# Trace_4__2_8TFT__AT32F435RGT7.net
KiCad netlist of a schematic drawn in EasyEDA Pro
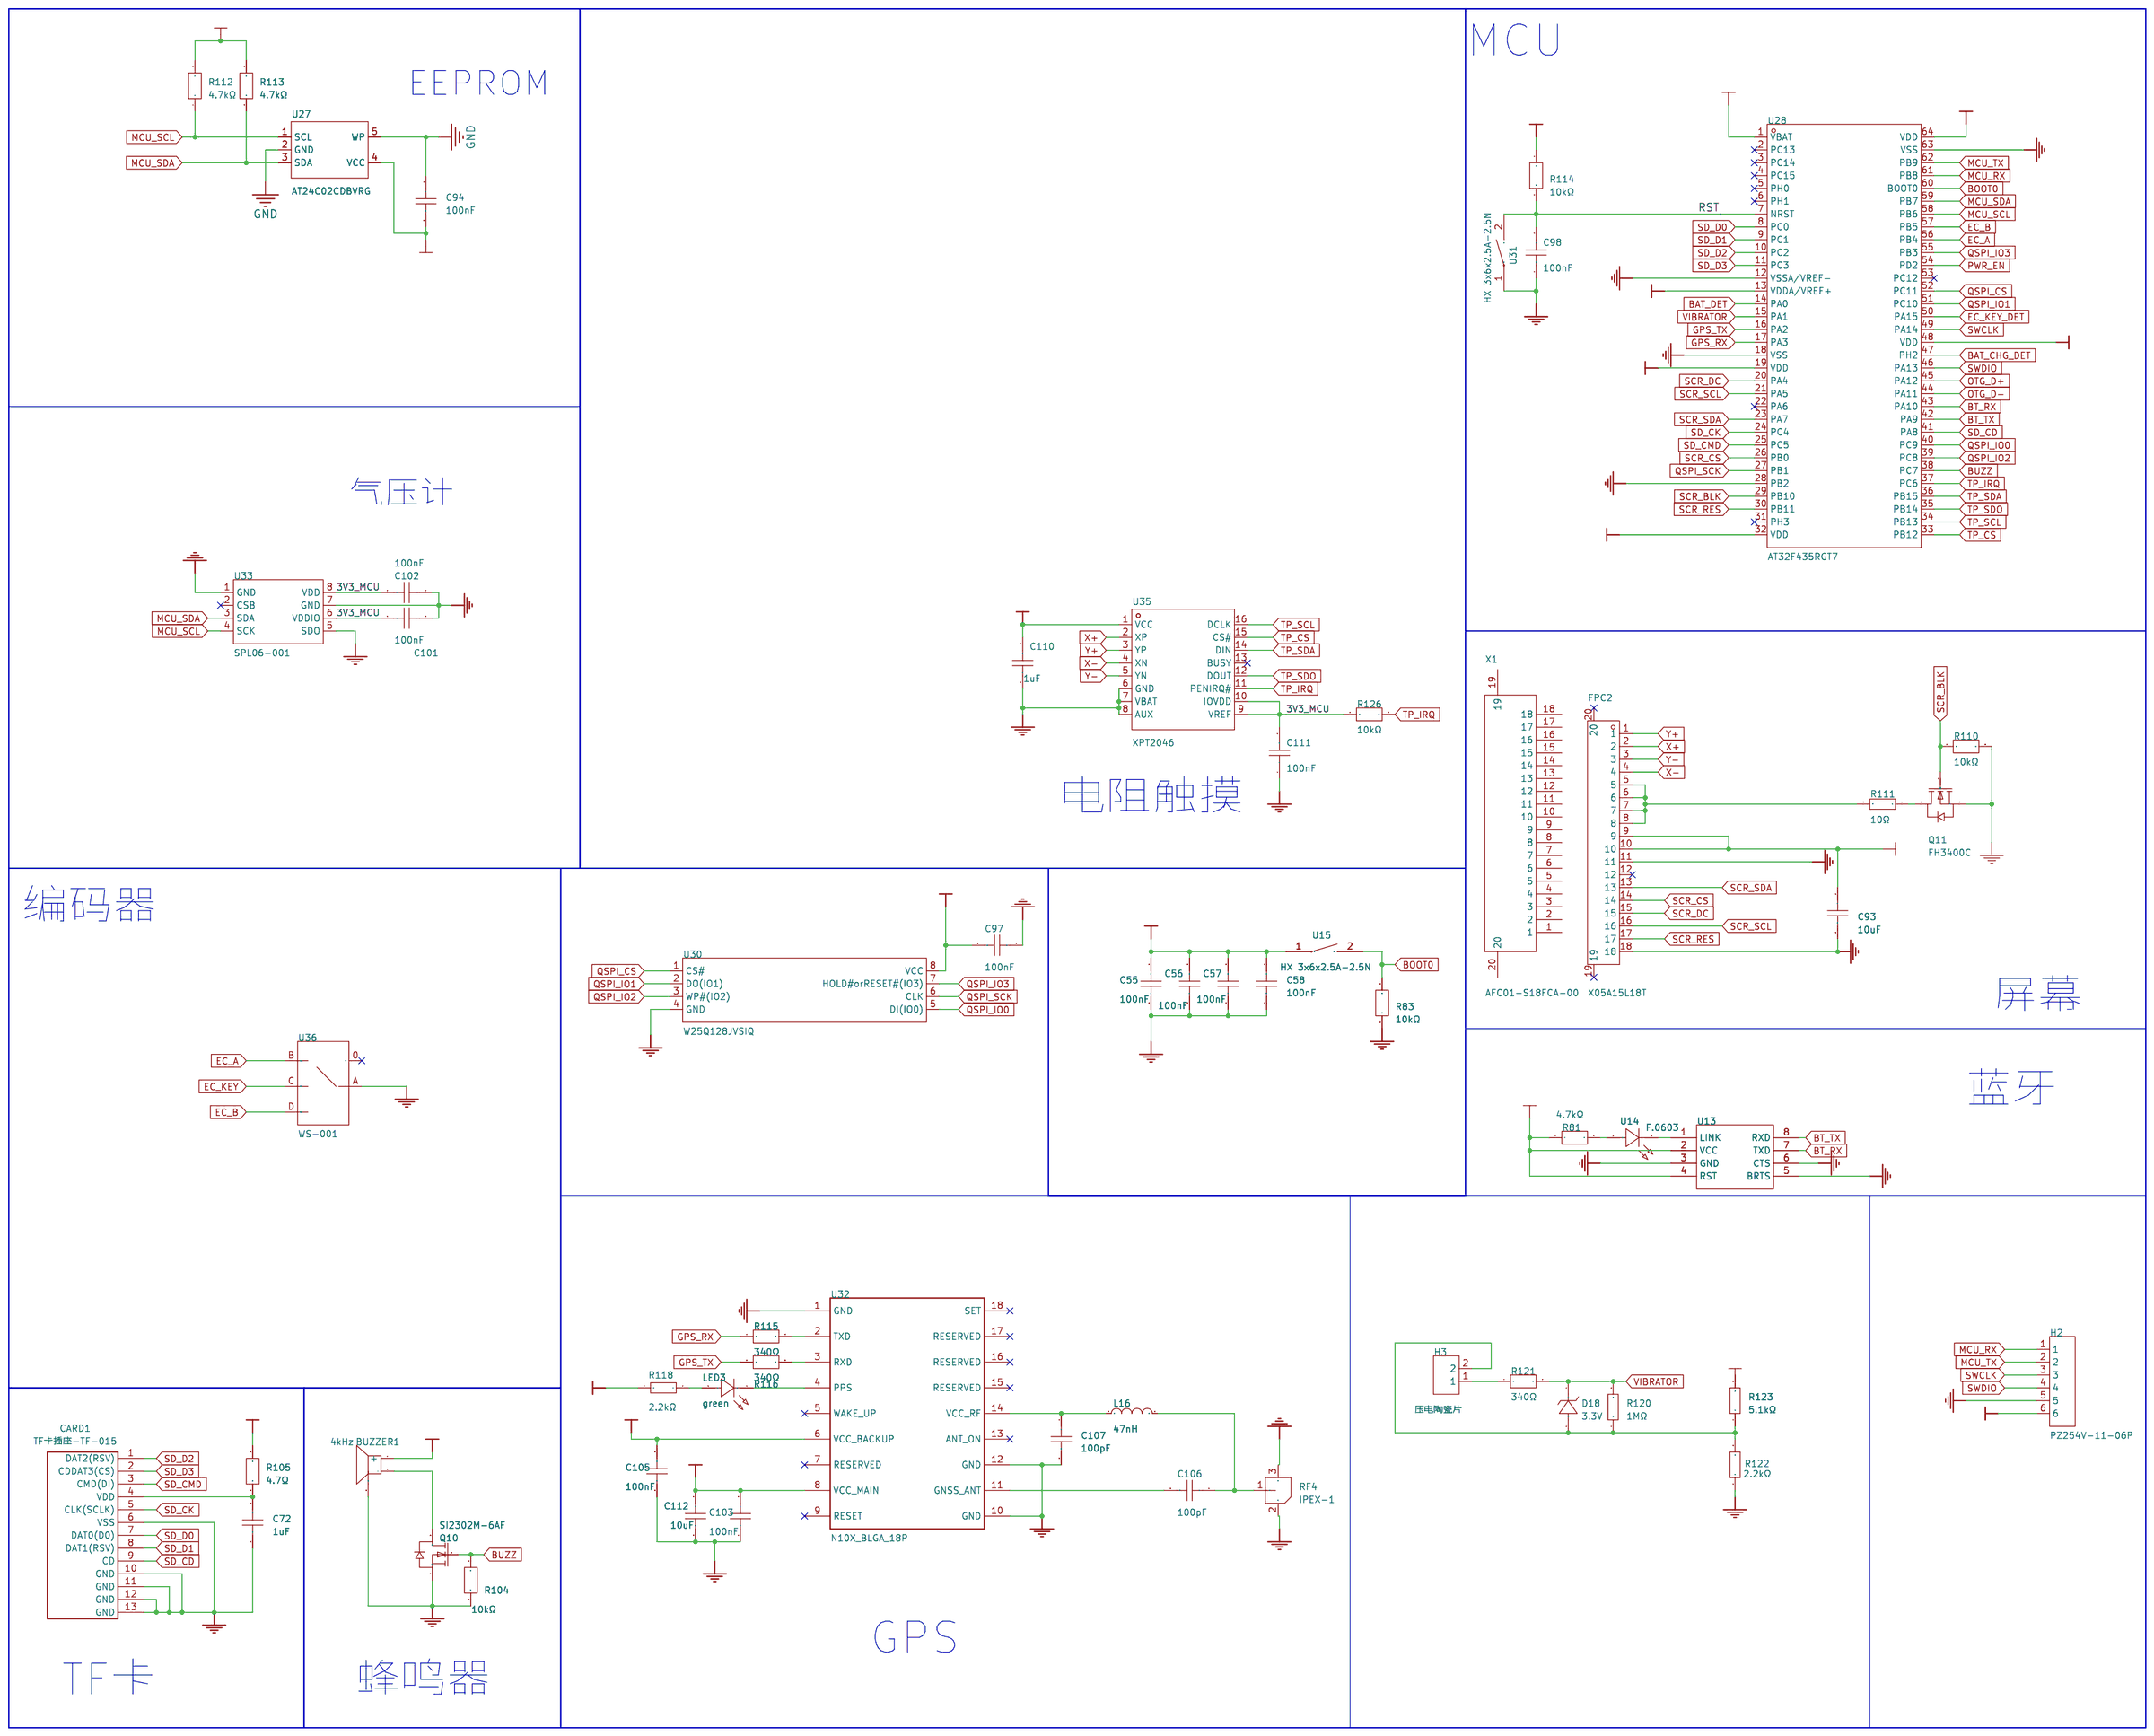
[diagram p0: Sheet_1 copy]
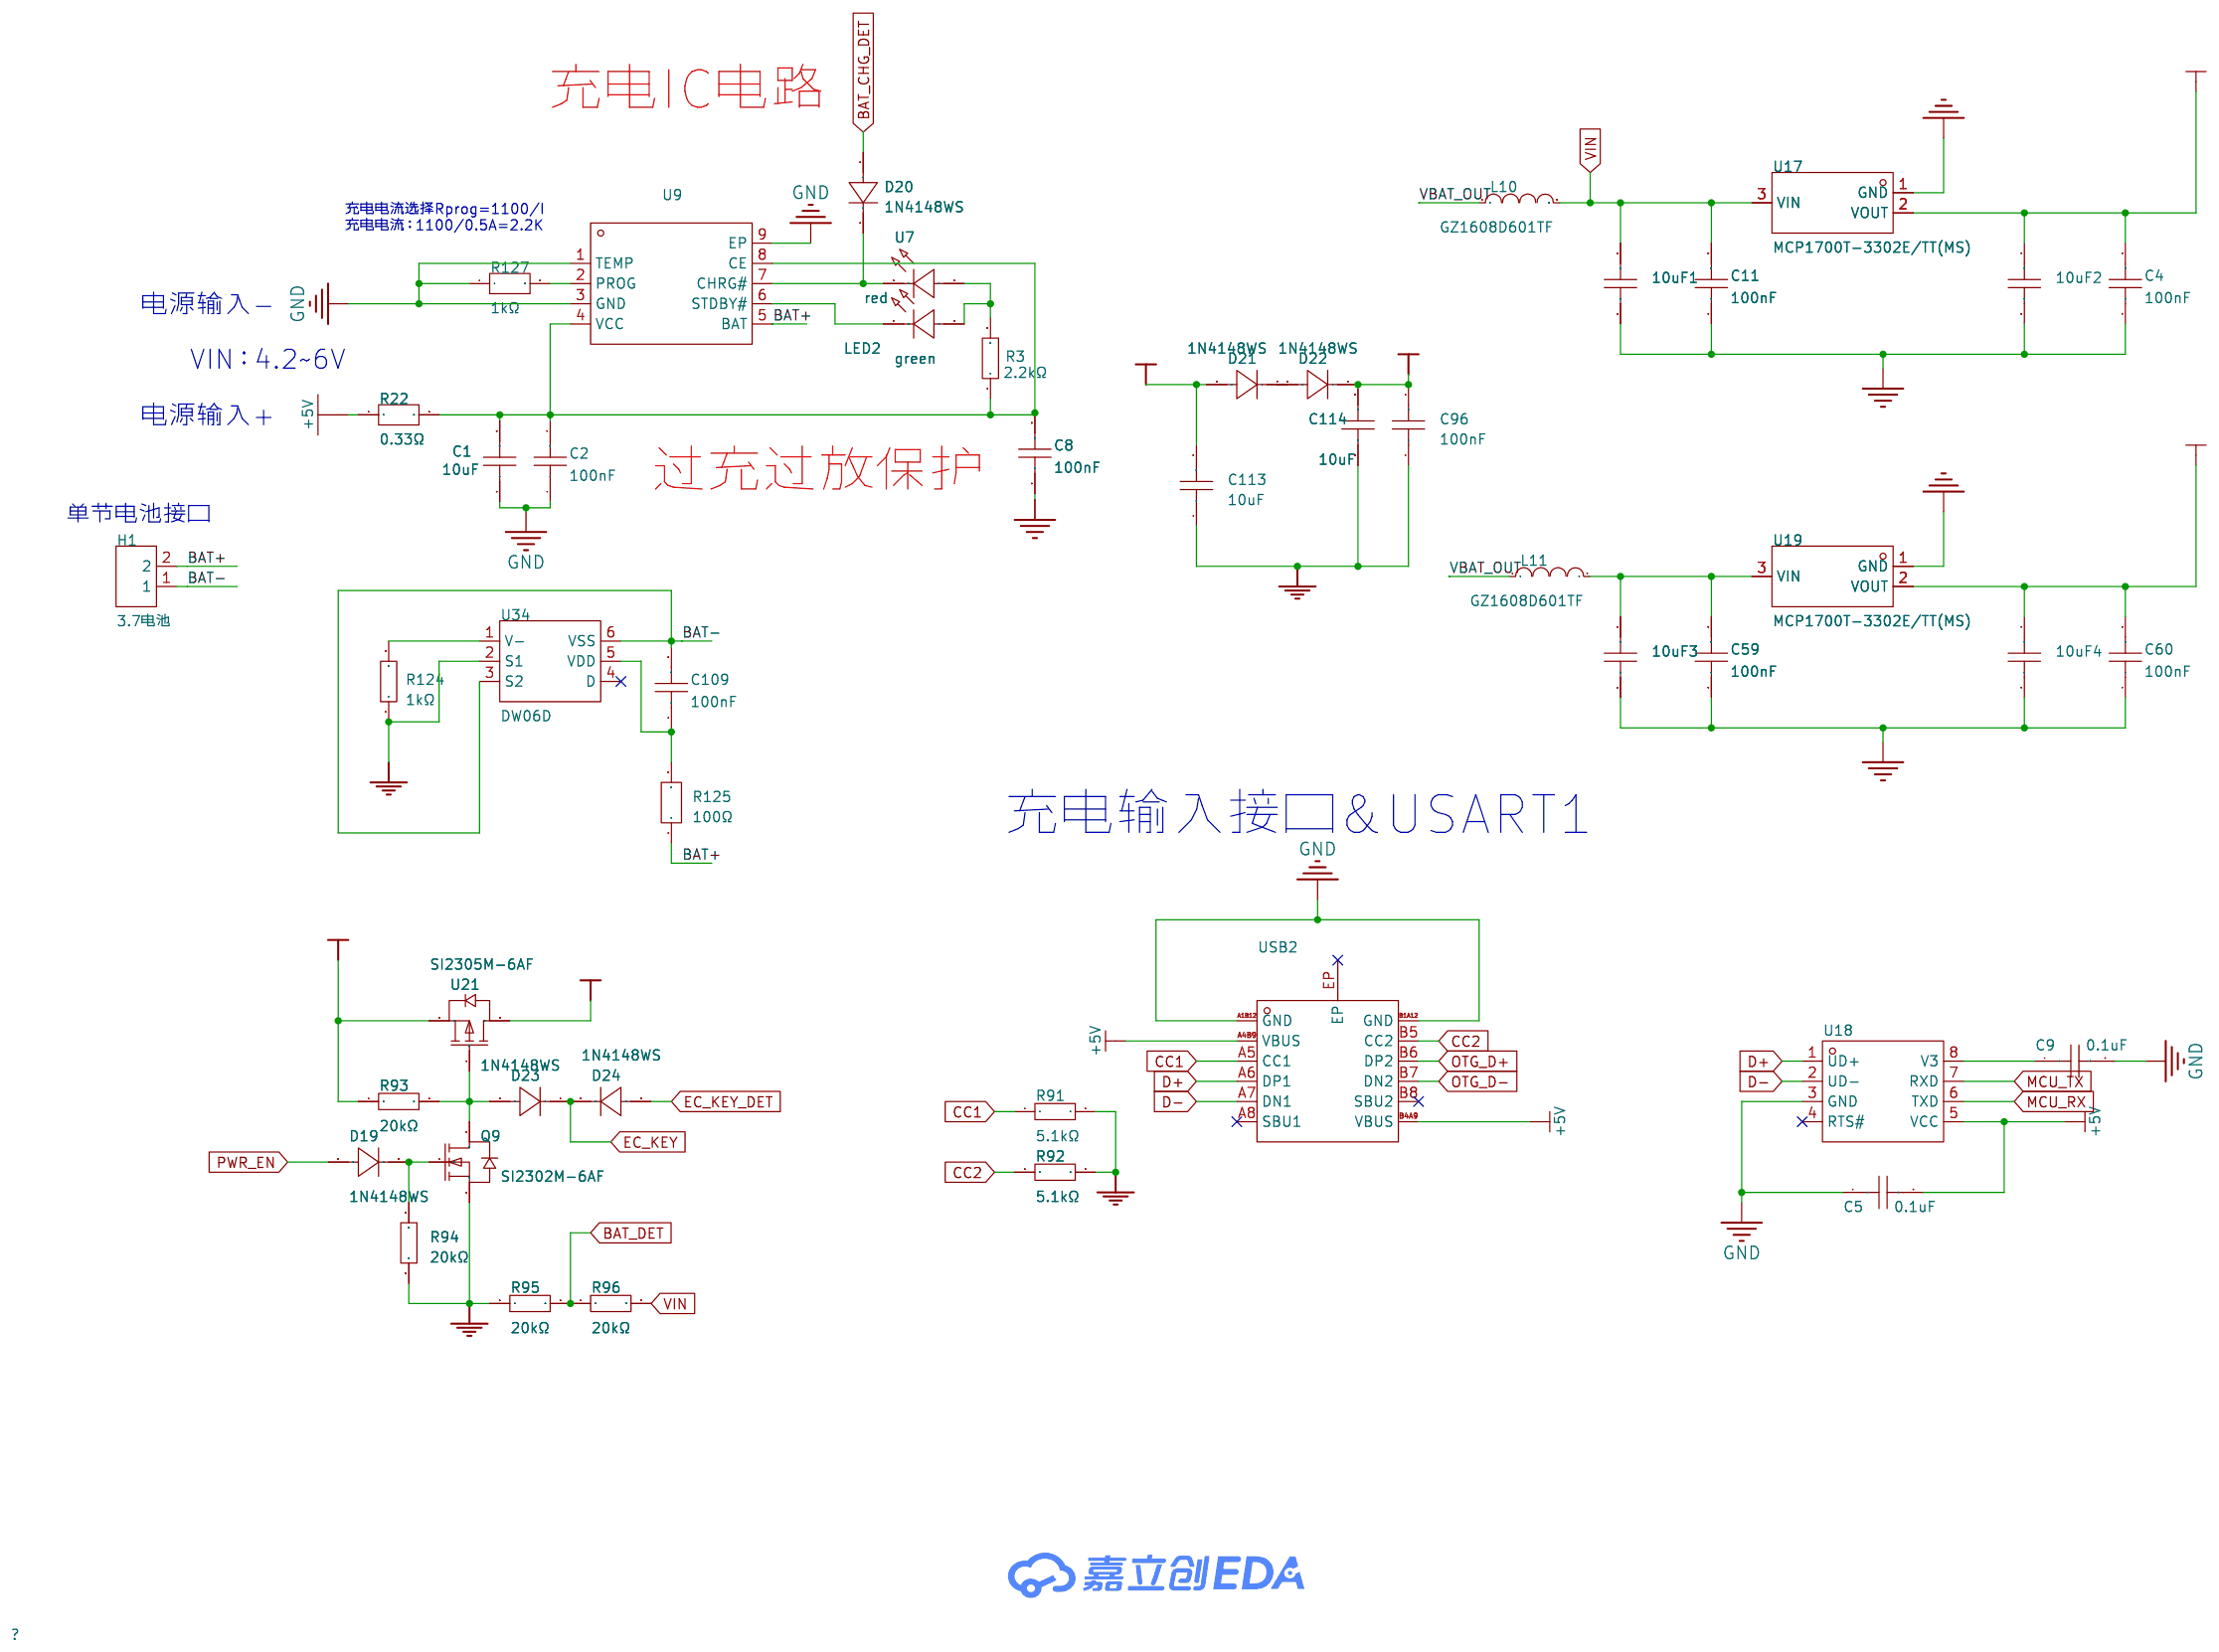
[diagram p1: Power_Supply]

(export (version "E")
  (design (tool "Eeschema 10.0.6"))
  (components
    (comp (ref "BUZZER1")
      (value "4kHz")
      (footprint "easyedapro:BUZ-SMD_3P-SMD5020-ZK")
      (description "驱动方式:无源(外部驱动);构造类型:电磁式;额定电压:3V;频率:4kHz;声压(SPL):78dB;")
      (fields (field (name "Manufacturer Part") "SMD5020-ZK") (field (name "Manufacturer") "XHXDZ(兴华鑫)"))
      (libsource (lib "easyedapro") (part "SMD5020-ZK"))
    )
    (comp (ref "C55")
      (value "100nF")
      (footprint "easyedapro:C0603")
      (description "容值:100nF;精度:±10%;额定电压:50V;温度系数:X7R;")
      (fields
        (field (name "Manufacturer Part") "CC0603KRX7R9BB104")
        (field (name "Manufacturer") "YAGEO(国巨)")
      )
      (libsource (lib "easyedapro") (part "CC0603KRX7R9BB104"))
    )
    (comp (ref "C56")
      (value "100nF")
      (footprint "easyedapro:C0603")
      (description "容值:100nF;精度:±10%;额定电压:50V;温度系数:X7R;")
      (fields
        (field (name "Manufacturer Part") "CC0603KRX7R9BB104")
        (field (name "Manufacturer") "YAGEO(国巨)")
      )
      (libsource (lib "easyedapro") (part "CC0603KRX7R9BB104"))
    )
    (comp (ref "C57")
      (value "100nF")
      (footprint "easyedapro:C0603")
      (description "容值:100nF;精度:±10%;额定电压:50V;温度系数:X7R;")
      (fields
        (field (name "Manufacturer Part") "CC0603KRX7R9BB104")
        (field (name "Manufacturer") "YAGEO(国巨)")
      )
      (libsource (lib "easyedapro") (part "CC0603KRX7R9BB104"))
    )
    (comp (ref "C58")
      (value "100nF")
      (footprint "easyedapro:C0603")
      (description "容值:100nF;精度:±10%;额定电压:50V;温度系数:X7R;")
      (fields
        (field (name "Manufacturer Part") "CC0603KRX7R9BB104")
        (field (name "Manufacturer") "YAGEO(国巨)")
      )
      (libsource (lib "easyedapro") (part "CC0603KRX7R9BB104"))
    )
    (comp (ref "C72")
      (value "1uF")
      (footprint "easyedapro:C0603")
      (description "容值:1uF;精度:±10%;额定电压:16V;温度系数:X5R;")
      (fields
        (field (name "Manufacturer Part") "CGA0603X5R105K160JT")
        (field (name "Manufacturer") "HRE(芯声)")
      )
      (libsource (lib "easyedapro") (part "CGA0603X5R105K160JT"))
    )
    (comp (ref "C93")
      (value "10uF")
      (footprint "easyedapro:C0603")
      (description "容值:10uF;精度:±10%;额定电压:10V;温度系数:X5R;")
      (fields
        (field (name "Manufacturer Part") "CGA0603X5R106K100JT")
        (field (name "Manufacturer") "HRE(芯声)")
      )
      (libsource (lib "easyedapro") (part "CGA0603X5R106K100JT"))
    )
    (comp (ref "C94")
      (value "100nF")
      (footprint "easyedapro:C0603")
      (description "容值:100nF;精度:±10%;额定电压:50V;温度系数:X7R;")
      (fields
        (field (name "Manufacturer Part") "CC0603KRX7R9BB104")
        (field (name "Manufacturer") "YAGEO(国巨)")
      )
      (libsource (lib "easyedapro") (part "CC0603KRX7R9BB104"))
    )
    (comp (ref "C97")
      (value "100nF")
      (footprint "easyedapro:C0603")
      (description "容值:100nF;精度:±10%;额定电压:50V;温度系数:X7R;")
      (fields
        (field (name "Manufacturer Part") "CC0603KRX7R9BB104")
        (field (name "Manufacturer") "YAGEO(国巨)")
      )
      (libsource (lib "easyedapro") (part "CC0603KRX7R9BB104"))
    )
    (comp (ref "C98")
      (value "100nF")
      (footprint "easyedapro:C0603")
      (description "容值:100nF;精度:±10%;额定电压:50V;温度系数:X7R;")
      (fields
        (field (name "Manufacturer Part") "CC0603KRX7R9BB104")
        (field (name "Manufacturer") "YAGEO(国巨)")
      )
      (libsource (lib "easyedapro") (part "CC0603KRX7R9BB104"))
    )
    (comp (ref "C101")
      (value "100nF")
      (footprint "easyedapro:C0603")
      (description "容值:100nF;精度:±10%;额定电压:50V;温度系数:X7R;")
      (fields
        (field (name "Manufacturer Part") "CC0603KRX7R9BB104")
        (field (name "Manufacturer") "YAGEO(国巨)")
      )
      (libsource (lib "easyedapro") (part "CC0603KRX7R9BB104"))
    )
    (comp (ref "C102")
      (value "100nF")
      (footprint "easyedapro:C0603")
      (description "容值:100nF;精度:±10%;额定电压:50V;温度系数:X7R;")
      (fields
        (field (name "Manufacturer Part") "CC0603KRX7R9BB104")
        (field (name "Manufacturer") "YAGEO(国巨)")
      )
      (libsource (lib "easyedapro") (part "CC0603KRX7R9BB104"))
    )
    (comp (ref "C103")
      (value "100nF")
      (footprint "easyedapro:C0603")
      (description "容值:100nF;精度:±10%;额定电压:50V;温度系数:X7R;")
      (fields
        (field (name "Manufacturer Part") "CC0603KRX7R9BB104")
        (field (name "Manufacturer") "YAGEO(国巨)")
      )
      (libsource (lib "easyedapro") (part "CC0603KRX7R9BB104"))
    )
    (comp (ref "C105")
      (value "100nF")
      (footprint "easyedapro:C0603")
      (description "容值:100nF;精度:±10%;额定电压:50V;温度系数:X7R;")
      (fields
        (field (name "Manufacturer Part") "CC0603KRX7R9BB104")
        (field (name "Manufacturer") "YAGEO(国巨)")
      )
      (libsource (lib "easyedapro") (part "CC0603KRX7R9BB104"))
    )
    (comp (ref "C106")
      (value "100pF")
      (footprint "easyedapro:C0603")
      (description "容值:100pF;精度:±5%;额定电压:50V;温度系数:C0G;")
      (fields
        (field (name "Manufacturer Part") "CGA0603C0G101J500JT")
        (field (name "Manufacturer") "HRE(芯声)")
      )
      (libsource (lib "easyedapro") (part "CGA0603C0G101J500JT"))
    )
    (comp (ref "C107")
      (value "100pF")
      (footprint "easyedapro:C0603")
      (description "容值:100pF;精度:±5%;额定电压:50V;温度系数:C0G;")
      (fields
        (field (name "Manufacturer Part") "CGA0603C0G101J500JT")
        (field (name "Manufacturer") "HRE(芯声)")
      )
      (libsource (lib "easyedapro") (part "CGA0603C0G101J500JT"))
    )
    (comp (ref "C110")
      (value "1uF")
      (footprint "easyedapro:C0603")
      (description "容值:1uF;精度:±10%;额定电压:50V;温度系数:X5R;")
      (fields
        (field (name "Manufacturer Part") "CL10A105KB8NNNC")
        (field (name "Manufacturer") "SAMSUNG(三星)")
      )
      (libsource (lib "easyedapro") (part "CL10A105KB8NNNC"))
    )
    (comp (ref "C111")
      (value "100nF")
      (footprint "easyedapro:C0603")
      (description "容值:100nF;精度:±10%;额定电压:50V;温度系数:X7R;")
      (fields
        (field (name "Manufacturer Part") "CC0603KRX7R9BB104")
        (field (name "Manufacturer") "YAGEO(国巨)")
      )
      (libsource (lib "easyedapro") (part "CC0603KRX7R9BB104"))
    )
    (comp (ref "C112")
      (value "10uF")
      (footprint "easyedapro:C0603")
      (description "容值:10uF;精度:±20%;额定电压:25V;温度系数:X5R;")
      (fields
        (field (name "Manufacturer Part") "CL10A106MA8NRNC")
        (field (name "Manufacturer") "SAMSUNG(三星)")
      )
      (libsource (lib "easyedapro") (part "CL10A106MA8NRNC"))
    )
    (comp (ref "CARD1")
      (value "TF卡插座-TF-015")
      (footprint "easyedapro:TF卡插座-TF-015")
      (fields
        (field (name "Manufacturer Part") "TF-015")
        (field (name "Manufacturer") "SOFNG")
        (field (name "Contributor") "DoM")
      )
      (libsource (lib "easyedapro") (part "TF卡插座-TF-015"))
    )
    (comp (ref "D18")
      (value "3.3V")
      (footprint "easyedapro:SOD-323_L1.7-W1.3-LS2.6-RD")
      (description "二极管配置:独立式;稳压值(标称值):3.3V;稳压值(范围):3.1V~3.5V;耗散功率(Pd):200mW;")
      (fields (field (name "Manufacturer") "宏嘉诚"))
      (libsource (lib "easyedapro") (part "BZT52C3V3S_C19077437"))
    )
    (comp (ref "FPC2")
      (value "X05A15L18T")
      (footprint "easyedapro:FFC-SMD_18P-P0.50_X05A15L18T")
      (description "锁定特性:翻盖式;触点类型:下接;触点数量:18P;间距:0.5mm;安装类型:卧贴;工作温度范围:-25°C~+85°C;焊接温度(最大值):260°C;")
      (fields (field (name "Manufacturer") "XKB Connectivity(中国星坤)"))
      (libsource (lib "easyedapro") (part "X05A15L18T"))
    )
    (comp (ref "H2")
      (value "PZ254V-11-06P")
      (footprint "easyedapro:HDR-TH_6P-P2.54-V-M")
      (fields (field (name "Manufacturer") "XFCN(兴飞)"))
      (libsource (lib "easyedapro") (part "PZ254V-11-06P"))
    )
    (comp (ref "H3")
      (value "压电陶瓷片")
      (footprint "easyedapro:HDR-TH_2P-P2.54-V-M")
      (fields (field (name "Manufacturer") "XFCN(兴飞)"))
      (libsource (lib "easyedapro") (part "PZ254V-11-02P"))
    )
    (comp (ref "L16")
      (value "47nH")
      (footprint "easyedapro:IND-SMD_L1.8-W1.0")
      (description "电感值:47nH;精度:±5%;额定电流:600mA;直流电阻(DCR):280mΩ;")
      (fields (field (name "Manufacturer Part") "AHW1608C-47NJTF") (field (name "Manufacturer") "APV(爱普微)"))
      (libsource (lib "easyedapro") (part "AHW1608C-47NJTF"))
    )
    (comp (ref "LED3")
      (value "green")
      (footprint "easyedapro:LED0603-RD_GREEN")
      (description "发光颜色:翠绿色;正向压降(Vf):2.6V~2.9V;正向电流:-;波长:520nm~525nm;透镜颜色:-;发光强度:230mcd;发光角度:120°;工作温度:-40°C~+85°C;")
      (fields (field (name "Manufacturer") "TUOZHAN(拓展光电)"))
      (libsource (lib "easyedapro") (part "F.0603.00025/P2-0603G1TS2-06T-002"))
    )
    (comp (ref "Q10")
      (value "SI2302M-6AF")
      (footprint "easyedapro:SOT-23-3_L2.9-W1.3-P1.90-LS2.4-BR")
      (description "数量:1个N沟道;漏源电压(Vdss):20V;连续漏极电流(Id):4.3A;导通电阻(RDS(on)):22mΩ@4.5V;耗散功率(Pd):1.2W;阈值电压(Vgs(th)):700mV;")
      (fields (field (name "Manufacturer") "FOSAN(富捷/富信)"))
      (libsource (lib "easyedapro") (part "SI2302M-6AF"))
    )
    (comp (ref "Q11")
      (value "FH3400C")
      (footprint "easyedapro:SOT-23-3_L2.9-W1.3-P1.90-LS2.4-BR")
      (fields (field (name "Manufacturer") "鑫飞宏"))
      (libsource (lib "easyedapro") (part "FH3400C"))
    )
    (comp (ref "R81")
      (value "4.7kΩ")
      (footprint "easyedapro:R0603")
      (description "电阻类型:厚膜电阻;阻值:4.7kΩ;精度:±5%;功率:100mW;最大工作电压:75V;温度系数:±100ppm/°C;")
      (fields (field (name "Manufacturer Part") "FRC0603J472 TS") (field (name "Manufacturer") "FOJAN(富捷)"))
      (libsource (lib "easyedapro") (part "FRC0603J472 TS"))
    )
    (comp (ref "R83")
      (value "10kΩ")
      (footprint "easyedapro:R0603")
      (description "电阻类型:厚膜电阻;阻值:10kΩ;精度:±5%;功率:100mW;工作电压:75V;温度系数:±100ppm/°C;")
      (fields (field (name "Manufacturer Part") "FRC0603J103 TS") (field (name "Manufacturer") "FOJAN(富捷)"))
      (libsource (lib "easyedapro") (part "FRC0603J103TS"))
    )
    (comp (ref "R104")
      (value "10kΩ")
      (footprint "easyedapro:R0603")
      (description "电阻类型:厚膜电阻;阻值:10kΩ;精度:±5%;功率:100mW;工作电压:75V;温度系数:±100ppm/°C;")
      (fields (field (name "Manufacturer Part") "FRC0603J103 TS") (field (name "Manufacturer") "FOJAN(富捷)"))
      (libsource (lib "easyedapro") (part "FRC0603J103TS"))
    )
    (comp (ref "R105")
      (value "4.7Ω")
      (footprint "easyedapro:R0603")
      (description "电阻类型:厚膜电阻;阻值:4.7Ω;精度:±5%;功率:100mW;工作电压:75V;温度系数:±200ppm/°C;")
      (fields (field (name "Manufacturer Part") "FRC0603J4R7 TS") (field (name "Manufacturer") "FOJAN(富捷)"))
      (libsource (lib "easyedapro") (part "FRC0603J4R7 TS"))
    )
    (comp (ref "R110")
      (value "10kΩ")
      (footprint "easyedapro:R0603")
      (description "电阻类型:厚膜电阻;阻值:10kΩ;精度:±5%;功率:100mW;工作电压:75V;温度系数:±100ppm/°C;")
      (fields (field (name "Manufacturer Part") "FRC0603J103 TS") (field (name "Manufacturer") "FOJAN(富捷)"))
      (libsource (lib "easyedapro") (part "FRC0603J103TS"))
    )
    (comp (ref "R111")
      (value "10Ω")
      (footprint "easyedapro:R0603")
      (description "电阻类型:厚膜电阻;阻值:10Ω;精度:±1%;功率:100mW;最大工作电压:75V;温度系数:±400ppm/°C;")
      (fields
        (field (name "Manufacturer Part") "0603WAF100JT5E")
        (field (name "Manufacturer") "UNI-ROYAL(厚声)")
      )
      (libsource (lib "easyedapro") (part "0603WAF100JT5E"))
    )
    (comp (ref "R112")
      (value "4.7kΩ")
      (footprint "easyedapro:R0603")
      (description "电阻类型:厚膜电阻;阻值:4.7kΩ;精度:±5%;功率:100mW;最大工作电压:75V;温度系数:±100ppm/°C;")
      (fields (field (name "Manufacturer Part") "FRC0603J472 TS") (field (name "Manufacturer") "FOJAN(富捷)"))
      (libsource (lib "easyedapro") (part "FRC0603J472 TS"))
    )
    (comp (ref "R113")
      (value "4.7kΩ")
      (footprint "easyedapro:R0603")
      (description "电阻类型:厚膜电阻;阻值:4.7kΩ;精度:±5%;功率:100mW;最大工作电压:75V;温度系数:±100ppm/°C;")
      (fields (field (name "Manufacturer Part") "FRC0603J472 TS") (field (name "Manufacturer") "FOJAN(富捷)"))
      (libsource (lib "easyedapro") (part "FRC0603J472 TS"))
    )
    (comp (ref "R114")
      (value "10kΩ")
      (footprint "easyedapro:R0603")
      (description "电阻类型:厚膜电阻;阻值:10kΩ;精度:±5%;功率:100mW;工作电压:75V;温度系数:±100ppm/°C;")
      (fields (field (name "Manufacturer Part") "FRC0603J103 TS") (field (name "Manufacturer") "FOJAN(富捷)"))
      (libsource (lib "easyedapro") (part "FRC0603J103TS"))
    )
    (comp (ref "R115")
      (value "340Ω")
      (footprint "easyedapro:R0603")
      (description "电阻类型:厚膜电阻;阻值:330Ω;精度:±5%;功率:100mW;最大工作电压:75V;温度系数:±100ppm/°C;")
      (fields (field (name "Manufacturer Part") "FRC0603J331 TS") (field (name "Manufacturer") "FOJAN(富捷)"))
      (libsource (lib "easyedapro") (part "FRC0603J331 TS"))
    )
    (comp (ref "R116")
      (value "340Ω")
      (footprint "easyedapro:R0603")
      (description "电阻类型:厚膜电阻;阻值:330Ω;精度:±5%;功率:100mW;最大工作电压:75V;温度系数:±100ppm/°C;")
      (fields (field (name "Manufacturer Part") "FRC0603J331 TS") (field (name "Manufacturer") "FOJAN(富捷)"))
      (libsource (lib "easyedapro") (part "FRC0603J331 TS"))
    )
    (comp (ref "R118")
      (value "2.2kΩ")
      (footprint "easyedapro:R0603")
      (description "电阻类型:厚膜电阻;阻值:2.2kΩ;精度:±1%;功率:100mW;最大工作电压:75V;温度系数:±100ppm/°C;")
      (fields
        (field (name "Manufacturer Part") "0603WAF2201T5E")
        (field (name "Manufacturer") "UNI-ROYAL(厚声)")
      )
      (libsource (lib "easyedapro") (part "0603WAF2201T5E"))
    )
    (comp (ref "R120")
      (value "1MΩ")
      (footprint "easyedapro:R0603")
      (description "电阻类型:厚膜电阻;阻值:1MΩ;精度:±1%;功率:100mW;最大工作电压:75V;温度系数:±100ppm/°C;")
      (fields
        (field (name "Manufacturer Part") "0603WAF1004T5E")
        (field (name "Manufacturer") "UNI-ROYAL(厚声)")
      )
      (libsource (lib "easyedapro") (part "0603WAF1004T5E"))
    )
    (comp (ref "R121")
      (value "340Ω")
      (footprint "easyedapro:R0603")
      (description "电阻类型:厚膜电阻;阻值:330Ω;精度:±5%;功率:100mW;最大工作电压:75V;温度系数:±100ppm/°C;")
      (fields (field (name "Manufacturer Part") "FRC0603J331 TS") (field (name "Manufacturer") "FOJAN(富捷)"))
      (libsource (lib "easyedapro") (part "FRC0603J331 TS"))
    )
    (comp (ref "R122")
      (value "2.2kΩ")
      (footprint "easyedapro:R0603")
      (description "电阻类型:厚膜电阻;阻值:2.2kΩ;精度:±1%;功率:100mW;最大工作电压:75V;温度系数:±100ppm/°C;")
      (fields
        (field (name "Manufacturer Part") "0603WAF2201T5E")
        (field (name "Manufacturer") "UNI-ROYAL(厚声)")
      )
      (libsource (lib "easyedapro") (part "0603WAF2201T5E"))
    )
    (comp (ref "R123")
      (value "5.1kΩ")
      (footprint "easyedapro:R0603")
      (description "电阻类型:厚膜电阻;阻值:5.1kΩ;精度:±1%;功率:100mW;工作电压:75V;温度系数:±100ppm/°C;")
      (fields
        (field (name "Manufacturer Part") "0603WAF5101T5E")
        (field (name "Manufacturer") "UNI-ROYAL(厚声)")
      )
      (libsource (lib "easyedapro") (part "0603WAF5101T5E"))
    )
    (comp (ref "R126")
      (value "10kΩ")
      (footprint "easyedapro:R0603")
      (description "电阻类型:厚膜电阻;阻值:10kΩ;精度:±5%;功率:100mW;工作电压:75V;温度系数:±100ppm/°C;")
      (fields (field (name "Manufacturer Part") "FRC0603J103 TS") (field (name "Manufacturer") "FOJAN(富捷)"))
      (libsource (lib "easyedapro") (part "FRC0603J103TS"))
    )
    (comp (ref "RF4")
      (value "IPEX-1")
      (footprint "easyedapro:IPEX-SMD_3P-L2.6-W2.6-LS3.0_RF1200001R")
      (description "RF座 IPEX天线座1代 高1.25")
      (fields (field (name "Manufacturer") "HanElectricity(瀚源)"))
      (libsource (lib "easyedapro") (part "IPEX-1_C47986640"))
    )
    (comp (ref "U13")
      (value "~")
      (footprint "easyedapro:XY-MBO35A")
      (libsource (lib "easyedapro") (part "XY-MBO35A"))
    )
    (comp (ref "U14")
      (value "F.0603")
      (footprint "easyedapro:LED0603-RD")
      (description "发光颜色:蓝色;正向电流:-;透镜颜色:-;发光角度:120°;工作温度:-40°C~+85°C;")
      (fields (field (name "Manufacturer") "TUOZHAN(拓展光电)"))
      (libsource (lib "easyedapro") (part "F.0603.00026/P2-0603B1TS2-06T-001"))
    )
    (comp (ref "U15")
      (value "HX 3x6x2.5A-2.5N")
      (footprint "easyedapro:SW-SMD_HX-TS-1101-C-W")
      (description "按钮形状:矩形按钮;作用力:2.5N;安装方式:立贴;开关长度:6mm;开关宽度:3.6mm;开关高度:2.5mm;带支架:-;触点电流:50mA;额定电压:12V;带灯:无;机械寿命:3万次;")
      (fields (field (name "Manufacturer") "hanxia(韩下)"))
      (libsource (lib "easyedapro") (part "HX TS-1101-C-W"))
    )
    (comp (ref "U27")
      (value "AT24C02CDBVRG")
      (footprint "easyedapro:SOT-23-5_L2.9-W1.6-P0.95-LS2.8-BR")
      (description "接口类型:I2C;存储容量:2Kbit;时钟频率(fc):1MHz;")
      (fields (field (name "Manufacturer") "HGC(深圳汉芯)"))
      (libsource (lib "easyedapro") (part "AT24C02CDBVRG"))
    )
    (comp (ref "U28")
      (value "AT32F435RGT7")
      (footprint "easyedapro:LQFP-64_L10.0-W10.0-P0.50-LS12.0-BL")
      (fields (field (name "Manufacturer") "ARTERY(雅特力)"))
      (libsource (lib "easyedapro") (part "AT32F435RGT7"))
    )
    (comp (ref "U30")
      (value "W25Q128JVSIQ")
      (footprint "easyedapro:SOIC-8_L5.3-W5.3-P1.27-LS8.0-BL")
      (description "接口类型:SPI;存储容量:-;时钟频率(fc):133MHz;")
      (fields (field (name "Manufacturer") "Winbond(华邦)"))
      (libsource (lib "easyedapro") (part "W25Q128JVSIQ"))
    )
    (comp (ref "U31")
      (value "HX 3x6x2.5A-2.5N")
      (footprint "easyedapro:SW-SMD_HX-TS-1101-C-W")
      (description "按钮形状:矩形按钮;作用力:2.5N;安装方式:立贴;开关长度:6mm;开关宽度:3.6mm;开关高度:2.5mm;带支架:-;触点电流:50mA;额定电压:12V;带灯:无;机械寿命:3万次;")
      (fields (field (name "Manufacturer") "hanxia(韩下)"))
      (libsource (lib "easyedapro") (part "HX TS-1101-C-W"))
    )
    (comp (ref "U32") (value "N10X_BLGA_18P") (libsource (lib "easyedapro") (part "N10X_BLGA_18P")))
    (comp (ref "U33")
      (value "SPL06-001")
      (footprint "easyedapro:SENSOR-SMD_SPL06-001")
      (description "压力范围:300hpa~1100hpa;接口类型:I2C；SPI;")
      (fields (field (name "Manufacturer") "Goertek(歌尔)"))
      (libsource (lib "easyedapro") (part "SPL06-001"))
    )
    (comp (ref "U35")
      (value "XPT2046")
      (footprint "easyedapro:TSSOP-16_L5.0-W4.4-P0.65-LS6.4-BL")
      (description "接口类型:-;")
      (fields (field (name "Manufacturer") "XPT(矽普特)"))
      (libsource (lib "easyedapro") (part "XPT2046"))
    )
    (comp (ref "U36")
      (value "WS-001")
      (footprint "easyedapro:SW-SMD_WS-001")
      (description "3脚拨轮长柄/有定位/黑底/三向")
      (fields (field (name "Manufacturer") "HANBO(汉博)"))
      (libsource (lib "easyedapro") (part "WS-001"))
    )
    (comp (ref "X1")
      (value "AFC01-S18FCA-00")
      (footprint "easyedapro:FPC-SMD_18P-P0.50_JS_AFC01-S18FCA-00")
      (description "锁定特性:翻盖式;触点类型:下接;触点数量:18P;间距:0.5mm;安装方式:卧贴;工作温度:-;")
      (fields (field (name "Manufacturer") "JS(钜硕电子)"))
      (libsource (lib "easyedapro") (part "AFC01-S18FCA-00"))
    )
    (comp (ref "10uF1")
      (value "10uF")
      (footprint "easyedapro:C0603")
      (libsource (lib "easyedapro") (part "CapAcitance"))
    )
    (comp (ref "10uF2")
      (value "10uF")
      (footprint "easyedapro:C0603")
      (libsource (lib "easyedapro") (part "CapAcitance"))
    )
    (comp (ref "10uF3")
      (value "10uF")
      (footprint "easyedapro:C0603")
      (libsource (lib "easyedapro") (part "CapAcitance"))
    )
    (comp (ref "10uF4")
      (value "10uF")
      (footprint "easyedapro:C0603")
      (libsource (lib "easyedapro") (part "CapAcitance"))
    )
    (comp (ref "C1")
      (value "10uF")
      (footprint "easyedapro:C0603")
      (description "容值:10uF;精度:±10%;额定电压:10V;材质(温度系数):X5R;")
      (fields
        (field (name "Manufacturer Part") "CL10A106KP8NNNC")
        (field (name "Manufacturer") "SAMSUNG(三星)")
      )
      (libsource (lib "easyedapro") (part "CL10A106KP8NNNC"))
    )
    (comp (ref "C2")
      (value "100nF")
      (fields
        (field (name "Manufacturer Part") "CC0603KRX7R9BB104")
        (field (name "Manufacturer") "YAGEO(国巨)")
      )
      (libsource (lib "easyedapro") (part "CC0603KRX7R9BB104"))
    )
    (comp (ref "C4")
      (value "100nF")
      (fields
        (field (name "Manufacturer Part") "CC0603KRX7R9BB104")
        (field (name "Manufacturer") "YAGEO(国巨)")
      )
      (libsource (lib "easyedapro") (part "CC0603KRX7R9BB104"))
    )
    (comp (ref "C5")
      (value "0.1uF")
      (footprint "easyedapro:C0603")
      (description "容值:100nF;精度:±10%;额定电压:50V;温度系数:X7R;")
      (libsource (lib "easyedapro") (part "C1210X7R475K630NT"))
    )
    (comp (ref "C8")
      (value "100nF")
      (fields
        (field (name "Manufacturer Part") "CC0603KRX7R9BB104")
        (field (name "Manufacturer") "YAGEO(国巨)")
      )
      (libsource (lib "easyedapro") (part "CC0603KRX7R9BB104"))
    )
    (comp (ref "C9")
      (value "0.1uF")
      (footprint "easyedapro:C0603")
      (description "容值:100nF;精度:±10%;额定电压:50V;温度系数:X7R;")
      (libsource (lib "easyedapro") (part "C1210X7R475K630NT"))
    )
    (comp (ref "C11")
      (value "100nF")
      (fields
        (field (name "Manufacturer Part") "CC0603KRX7R9BB104")
        (field (name "Manufacturer") "YAGEO(国巨)")
      )
      (libsource (lib "easyedapro") (part "CC0603KRX7R9BB104"))
    )
    (comp (ref "C59")
      (value "100nF")
      (fields
        (field (name "Manufacturer Part") "CC0603KRX7R9BB104")
        (field (name "Manufacturer") "YAGEO(国巨)")
      )
      (libsource (lib "easyedapro") (part "CC0603KRX7R9BB104"))
    )
    (comp (ref "C60")
      (value "100nF")
      (fields
        (field (name "Manufacturer Part") "CC0603KRX7R9BB104")
        (field (name "Manufacturer") "YAGEO(国巨)")
      )
      (libsource (lib "easyedapro") (part "CC0603KRX7R9BB104"))
    )
    (comp (ref "C96")
      (value "100nF")
      (fields
        (field (name "Manufacturer Part") "CC0603KRX7R9BB104")
        (field (name "Manufacturer") "YAGEO(国巨)")
      )
      (libsource (lib "easyedapro") (part "CC0603KRX7R9BB104"))
    )
    (comp (ref "C109")
      (value "100nF")
      (fields
        (field (name "Manufacturer Part") "CC0603KRX7R9BB104")
        (field (name "Manufacturer") "YAGEO(国巨)")
      )
      (libsource (lib "easyedapro") (part "CC0603KRX7R9BB104"))
    )
    (comp (ref "C113")
      (value "10uF")
      (footprint "easyedapro:C0603")
      (description "容值:10uF;精度:±20%;额定电压:25V;温度系数:X5R;")
      (fields
        (field (name "Manufacturer Part") "CL10A106MA8NRNC")
        (field (name "Manufacturer") "SAMSUNG(三星)")
      )
      (libsource (lib "easyedapro") (part "CL10A106MA8NRNC"))
    )
    (comp (ref "C114")
      (value "10uF")
      (footprint "easyedapro:C0603")
      (description "容值:10uF;精度:±20%;额定电压:25V;温度系数:X5R;")
      (fields
        (field (name "Manufacturer Part") "CL10A106MA8NRNC")
        (field (name "Manufacturer") "SAMSUNG(三星)")
      )
      (libsource (lib "easyedapro") (part "CL10A106MA8NRNC"))
    )
    (comp (ref "D19")
      (value "1N4148WS")
      (footprint "easyedapro:SOD-323_L1.8-W1.3-LS2.5-RD")
      (description "二极管配置:独立式;正向压降(Vf):1.25V@150mA;直流反向耐压(Vr):100V;整流电流:150mA;反向恢复时间(Trr):4ns;")
      (fields (field (name "Manufacturer") "GOODWORK(固得沃克)"))
      (libsource (lib "easyedapro") (part "1N4148WS_C909968"))
    )
    (comp (ref "D20")
      (value "1N4148WS")
      (footprint "easyedapro:SOD-323_L1.8-W1.3-LS2.5-RD")
      (description "二极管配置:独立式;正向压降(Vf):1.25V@150mA;直流反向耐压(Vr):100V;整流电流:150mA;反向恢复时间(Trr):4ns;")
      (fields (field (name "Manufacturer") "GOODWORK(固得沃克)"))
      (libsource (lib "easyedapro") (part "1N4148WS_C909968"))
    )
    (comp (ref "D21")
      (value "1N4148WS")
      (footprint "easyedapro:SOD-323_L1.8-W1.3-LS2.5-RD")
      (description "二极管配置:独立式;正向压降(Vf):1.25V@150mA;直流反向耐压(Vr):100V;整流电流:150mA;反向恢复时间(Trr):4ns;")
      (fields (field (name "Manufacturer") "GOODWORK(固得沃克)"))
      (libsource (lib "easyedapro") (part "1N4148WS_C909968"))
    )
    (comp (ref "D22")
      (value "1N4148WS")
      (footprint "easyedapro:SOD-323_L1.8-W1.3-LS2.5-RD")
      (description "二极管配置:独立式;正向压降(Vf):1.25V@150mA;直流反向耐压(Vr):100V;整流电流:150mA;反向恢复时间(Trr):4ns;")
      (fields (field (name "Manufacturer") "GOODWORK(固得沃克)"))
      (libsource (lib "easyedapro") (part "1N4148WS_C909968"))
    )
    (comp (ref "D23")
      (value "1N4148WS")
      (footprint "easyedapro:SOD-323_L1.8-W1.3-LS2.5-RD")
      (description "二极管配置:独立式;正向压降(Vf):1.25V@150mA;直流反向耐压(Vr):100V;整流电流:150mA;反向恢复时间(Trr):4ns;")
      (fields (field (name "Manufacturer") "GOODWORK(固得沃克)"))
      (libsource (lib "easyedapro") (part "1N4148WS_C909968"))
    )
    (comp (ref "D24")
      (value "1N4148WS")
      (footprint "easyedapro:SOD-323_L1.8-W1.3-LS2.5-RD")
      (description "二极管配置:独立式;正向压降(Vf):1.25V@150mA;直流反向耐压(Vr):100V;整流电流:150mA;反向恢复时间(Trr):4ns;")
      (fields (field (name "Manufacturer") "GOODWORK(固得沃克)"))
      (libsource (lib "easyedapro") (part "1N4148WS_C909968"))
    )
    (comp (ref "H1")
      (value "3.7电池")
      (footprint "easyedapro:HDR-TH_2P-P2.54-V-M")
      (fields (field (name "Manufacturer") "XFCN(兴飞)"))
      (libsource (lib "easyedapro") (part "PZ254V-11-02P"))
    )
    (comp (ref "L10")
      (value "GZ1608D601TF")
      (footprint "easyedapro:L0603")
      (description "阻抗 @ 频率:600Ω@100MHz;误差:±25%;直流电阻(DCR):450mΩ;")
      (fields (field (name "Manufacturer") "Sunlord(顺络)"))
      (libsource (lib "easyedapro") (part "GZ1608D601TF"))
    )
    (comp (ref "L11")
      (value "GZ1608D601TF")
      (footprint "easyedapro:L0603")
      (description "阻抗 @ 频率:600Ω@100MHz;误差:±25%;直流电阻(DCR):450mΩ;")
      (fields (field (name "Manufacturer") "Sunlord(顺络)"))
      (libsource (lib "easyedapro") (part "GZ1608D601TF"))
    )
    (comp (ref "LED2")
      (value "green")
      (footprint "easyedapro:LED0603-RD_GREEN")
      (description "发光颜色:翠绿色;正向压降(Vf):2.6V~2.9V;正向电流:-;波长:520nm~525nm;透镜颜色:-;发光强度:230mcd;发光角度:120°;工作温度:-40°C~+85°C;")
      (fields (field (name "Manufacturer") "TUOZHAN(拓展光电)"))
      (libsource (lib "easyedapro") (part "F.0603.00025/P2-0603G1TS2-06T-002"))
    )
    (comp (ref "Q9")
      (value "SI2302M-6AF")
      (footprint "easyedapro:SOT-23-3_L2.9-W1.3-P1.90-LS2.4-BR")
      (description "数量:1个N沟道;漏源电压(Vdss):20V;连续漏极电流(Id):4.3A;导通电阻(RDS(on)):22mΩ@4.5V;耗散功率(Pd):1.2W;阈值电压(Vgs(th)):700mV;")
      (fields (field (name "Manufacturer") "FOSAN(富捷/富信)"))
      (libsource (lib "easyedapro") (part "SI2302M-6AF"))
    )
    (comp (ref "R3")
      (value "2.2kΩ")
      (footprint "easyedapro:R0603")
      (description "电阻类型:厚膜电阻;阻值:2.2kΩ;精度:±1%;功率:100mW;最大工作电压:75V;温度系数:±100ppm/°C;")
      (fields
        (field (name "Manufacturer Part") "0603WAF2201T5E")
        (field (name "Manufacturer") "UNI-ROYAL(厚声)")
      )
      (libsource (lib "easyedapro") (part "0603WAF2201T5E"))
    )
    (comp (ref "R22")
      (value "0.33Ω")
      (footprint "easyedapro:R1206")
      (description "电阻类型:厚膜电阻;阻值:1Ω;精度:±1%;功率:250mW;工作电压:200V;温度系数:±200ppm/°C;")
      (fields
        (field (name "Manufacturer Part") "FRC1206F1R00TS")
        (field (name "Manufacturer") "Milliohm(毫欧)")
      )
      (libsource (lib "easyedapro") (part "FRC1206F1R00TS"))
    )
    (comp (ref "R91")
      (value "5.1kΩ")
      (footprint "easyedapro:R0603")
      (description "电阻类型:厚膜电阻;阻值:5.1kΩ;精度:±1%;功率:100mW;工作电压:75V;温度系数:±100ppm/°C;")
      (fields
        (field (name "Manufacturer Part") "0603WAF5101T5E")
        (field (name "Manufacturer") "UNI-ROYAL(厚声)")
      )
      (libsource (lib "easyedapro") (part "0603WAF5101T5E"))
    )
    (comp (ref "R92")
      (value "5.1kΩ")
      (footprint "easyedapro:R0603")
      (description "电阻类型:厚膜电阻;阻值:5.1kΩ;精度:±1%;功率:100mW;工作电压:75V;温度系数:±100ppm/°C;")
      (fields
        (field (name "Manufacturer Part") "0603WAF5101T5E")
        (field (name "Manufacturer") "UNI-ROYAL(厚声)")
      )
      (libsource (lib "easyedapro") (part "0603WAF5101T5E"))
    )
    (comp (ref "R93")
      (value "20kΩ")
      (footprint "easyedapro:R0603")
      (description "电阻类型:厚膜电阻;阻值:20kΩ;精度:±1%;功率:100mW;工作电压:75V;温度系数:±100ppm/°C;")
      (fields
        (field (name "Manufacturer Part") "0603WAF2002T5E")
        (field (name "Manufacturer") "UNI-ROYAL(厚声)")
      )
      (libsource (lib "easyedapro") (part "0603WAF2002T5E"))
    )
    (comp (ref "R94")
      (value "20kΩ")
      (footprint "easyedapro:R0603")
      (description "电阻类型:厚膜电阻;阻值:20kΩ;精度:±1%;功率:100mW;工作电压:75V;温度系数:±100ppm/°C;")
      (fields
        (field (name "Manufacturer Part") "0603WAF2002T5E")
        (field (name "Manufacturer") "UNI-ROYAL(厚声)")
      )
      (libsource (lib "easyedapro") (part "0603WAF2002T5E"))
    )
    (comp (ref "R95")
      (value "20kΩ")
      (footprint "easyedapro:R0603")
      (description "电阻类型:厚膜电阻;阻值:20kΩ;精度:±1%;功率:100mW;工作电压:75V;温度系数:±100ppm/°C;")
      (fields
        (field (name "Manufacturer Part") "0603WAF2002T5E")
        (field (name "Manufacturer") "UNI-ROYAL(厚声)")
      )
      (libsource (lib "easyedapro") (part "0603WAF2002T5E"))
    )
    (comp (ref "R96")
      (value "20kΩ")
      (footprint "easyedapro:R0603")
      (description "电阻类型:厚膜电阻;阻值:20kΩ;精度:±1%;功率:100mW;工作电压:75V;温度系数:±100ppm/°C;")
      (fields
        (field (name "Manufacturer Part") "0603WAF2002T5E")
        (field (name "Manufacturer") "UNI-ROYAL(厚声)")
      )
      (libsource (lib "easyedapro") (part "0603WAF2002T5E"))
    )
    (comp (ref "R124")
      (value "1kΩ")
      (footprint "easyedapro:R0603")
      (description "电阻类型:厚膜电阻;阻值:1kΩ;精度:±1%;功率:100mW;最大工作电压:75V;温度系数:±100ppm/°C;")
      (fields
        (field (name "Manufacturer Part") "0603WAF1001T5E")
        (field (name "Manufacturer") "UNI-ROYAL(厚声)")
      )
      (libsource (lib "easyedapro") (part "0603WAF1001T5E"))
    )
    (comp (ref "R125")
      (value "100Ω")
      (footprint "easyedapro:R0603")
      (description "电阻类型:陶瓷电阻;阻值:100Ω;精度:±0.1%;功率:100mW;温度系数:±25ppm/°C;")
      (fields
        (field (name "Manufacturer Part") "HoAR0603-1/10W-100R-0.1%-TCR25")
        (field (name "Manufacturer") "Milliohm(毫欧)")
      )
      (libsource (lib "easyedapro") (part "HOAR0603-1/10W-100R-0.1%-TCR25"))
    )
    (comp (ref "R127")
      (value "1kΩ")
      (footprint "easyedapro:R0603")
      (description "电阻类型:厚膜电阻;阻值:1kΩ;精度:±1%;功率:100mW;工作电压:75V;温度系数:±100ppm/°C;")
      (fields (field (name "Manufacturer Part") "FRC0603F1001TS") (field (name "Manufacturer") "FOJAN(富捷)"))
      (libsource (lib "easyedapro") (part "FRC0603F1001TS"))
    )
    (comp (ref "U7")
      (value "red")
      (footprint "easyedapro:LED0603-RD")
      (description "发光颜色:红色;正向电流:-;透镜颜色:-;发光角度:120°;工作温度:-40°C~+85°C;")
      (fields (field (name "Manufacturer") "TUOZHAN(拓展光电)"))
      (libsource (lib "easyedapro") (part "F.0603.00139/P2-0603R1TS2-06T-002"))
    )
    (comp (ref "U9")
      (value "~")
      (footprint "easyedapro:ESOP-8_L4.9-W3.9-P1.27-LS6.0-BL-EP")
      (fields (field (name "Manufacturer Part") "TP4056") (field (name "Manufacturer") "TPOWER(天源)"))
      (libsource (lib "easyedapro") (part "TP4056_C382139"))
    )
    (comp (ref "U17")
      (value "MCP1700T-3302E/TT(MS)")
      (footprint "easyedapro:SOT-23-3_L2.9-W1.3-P1.90-LS2.4-BR")
      (description "输出类型:固定;最大输入电压:5.5V;输出电压:3.3V;输出电流:300mA;电源纹波抑制比(PSRR):-;输出极性:正极;")
      (fields (field (name "Manufacturer") "MSKSEMI(美森科)"))
      (libsource (lib "easyedapro") (part "MCP1700T-3302E/TT(MS)"))
    )
    (comp (ref "U18")
      (value "~")
      (footprint "easyedapro:SOP-8_L4.9-W3.9-P1.27-LS6.0-BL")
      (fields (field (name "Manufacturer Part") "CH340N") (field (name "Manufacturer") "WCH(南京沁恒)"))
      (libsource (lib "easyedapro") (part "CH340N_C2977777"))
    )
    (comp (ref "U19")
      (value "MCP1700T-3302E/TT(MS)")
      (footprint "easyedapro:SOT-23-3_L2.9-W1.3-P1.90-LS2.4-BR")
      (description "输出类型:固定;最大输入电压:5.5V;输出电压:3.3V;输出电流:300mA;电源纹波抑制比(PSRR):-;输出极性:正极;")
      (fields (field (name "Manufacturer") "MSKSEMI(美森科)"))
      (libsource (lib "easyedapro") (part "MCP1700T-3302E/TT(MS)"))
    )
    (comp (ref "U21")
      (value "SI2305M-6AF")
      (footprint "easyedapro:SOT-23-3_L2.9-W1.3-P1.90-LS2.4-BR")
      (description "数量:1个P沟道;漏源电压(Vdss):20V;连续漏极电流(Id):5.5A;导通电阻(RDS(on)):29mΩ@4.5V;耗散功率(Pd):1.2W;阈值电压(Vgs(th)):620mV;")
      (fields (field (name "Manufacturer") "FOSAN(富捷/富信)"))
      (libsource (lib "easyedapro") (part "SI2305M-6AF"))
    )
    (comp (ref "U34")
      (value "DW06D")
      (footprint "easyedapro:SOT-23-6_L2.9-W1.6-P0.95-LS2.8-BR")
      (description "工作电压:1.5V~10V;最大充电电流:-;电池类型:锂离子/聚合物;电池节数:1;")
      (fields (field (name "Manufacturer") "GOODWORK(固得沃克)"))
      (libsource (lib "easyedapro") (part "DW06D_C22399520"))
    )
    (comp (ref "USB2")
      (value "~")
      (footprint "easyedapro:USB-C-SMD_TYPE-C-16P-1")
      (fields (field (name "Manufacturer Part") "TYPEC-304-ACP16") (field (name "Manufacturer") "XUNPU(讯普)"))
      (libsource (lib "easyedapro") (part "TYPEC-304-ACP16"))
    )
  )
  (nets
    (net (code "1") (name "+5V") (class "Default")
      (node (ref "C5") (pin "2") (pinfunction "2_2") (pintype "input"))
      (node (ref "R22") (pin "1") (pinfunction "1_1") (pintype "unspecified"))
      (node (ref "U18") (pin "5") (pinfunction "VCC_5") (pintype "input"))
      (node (ref "USB2") (pin "A4B9") (pinfunction "VBUS_A4B9") (pintype "input"))
      (node (ref "USB2") (pin "B4A9") (pinfunction "VBUS_B4A9") (pintype "input"))
    )
    (net (code "2") (name "3V3_GPS") (class "Default")
      (node (ref "10uF4") (pin "1") (pinfunction "1_1") (pintype "input"))
      (node (ref "C103") (pin "2") (pinfunction "2_2") (pintype "unspecified"))
      (node (ref "C112") (pin "1") (pinfunction "1_1") (pintype "unspecified"))
      (node (ref "C60") (pin "2") (pinfunction "2_2") (pintype "unspecified"))
      (node (ref "R118") (pin "2") (pinfunction "2_2") (pintype "input"))
      (node (ref "U19") (pin "2") (pinfunction "VOUT_2") (pintype "unspecified"))
      (node (ref "U32") (pin "8") (pinfunction "VCC_MAIN_8") (pintype "unspecified"))
    )
    (net (code "3") (name "3V3_MCU") (class "Default")
      (node (ref "10uF2") (pin "1") (pinfunction "1_1") (pintype "input"))
      (node (ref "BUZZER1") (pin "1") (pinfunction "+_1") (pintype "unspecified"))
      (node (ref "C101") (pin "2") (pinfunction "2_2") (pintype "unspecified"))
      (node (ref "C102") (pin "2") (pinfunction "2_2") (pintype "unspecified"))
      (node (ref "C110") (pin "2") (pinfunction "2_2") (pintype "unspecified"))
      (node (ref "C111") (pin "2") (pinfunction "2_2") (pintype "unspecified"))
      (node (ref "C4") (pin "2") (pinfunction "2_2") (pintype "unspecified"))
      (node (ref "C55") (pin "2") (pinfunction "2_2") (pintype "unspecified"))
      (node (ref "C56") (pin "2") (pinfunction "2_2") (pintype "unspecified"))
      (node (ref "C57") (pin "2") (pinfunction "2_2") (pintype "unspecified"))
      (node (ref "C58") (pin "2") (pinfunction "2_2") (pintype "unspecified"))
      (node (ref "C93") (pin "1") (pinfunction "1_1") (pintype "unspecified"))
      (node (ref "C94") (pin "2") (pinfunction "2_2") (pintype "unspecified"))
      (node (ref "C97") (pin "2") (pinfunction "2_2") (pintype "unspecified"))
      (node (ref "FPC2") (pin "10") (pinfunction "10_10") (pintype "unspecified"))
      (node (ref "FPC2") (pin "9") (pinfunction "9_9") (pintype "unspecified"))
      (node (ref "H2") (pin "6") (pinfunction "6_6") (pintype "unspecified"))
      (node (ref "R105") (pin "2") (pinfunction "2_2") (pintype "unspecified"))
      (node (ref "R112") (pin "2") (pinfunction "2_2") (pintype "unspecified"))
      (node (ref "R113") (pin "2") (pinfunction "2_2") (pintype "unspecified"))
      (node (ref "R114") (pin "1") (pinfunction "1_1") (pintype "unspecified"))
      (node (ref "R123") (pin "2") (pinfunction "2_2") (pintype "input"))
      (node (ref "R126") (pin "1") (pinfunction "1_1") (pintype "unspecified"))
      (node (ref "R81") (pin "1") (pinfunction "1_1") (pintype "unspecified"))
      (node (ref "U13") (pin "2") (pinfunction "VCC_2") (pintype "input"))
      (node (ref "U13") (pin "4") (pinfunction "RST_4") (pintype "input"))
      (node (ref "U15") (pin "1") (pinfunction "1_1") (pintype "unspecified"))
      (node (ref "U17") (pin "2") (pinfunction "VOUT_2") (pintype "unspecified"))
      (node (ref "U27") (pin "4") (pinfunction "VCC_4") (pintype "unspecified"))
      (node (ref "U28") (pin "13") (pinfunction "VDDA/VREF+_13") (pintype "unspecified"))
      (node (ref "U28") (pin "19") (pinfunction "VDD_19") (pintype "unspecified"))
      (node (ref "U28") (pin "32") (pinfunction "VDD_32") (pintype "unspecified"))
      (node (ref "U28") (pin "48") (pinfunction "VDD_48") (pintype "unspecified"))
      (node (ref "U28") (pin "64") (pinfunction "VDD_64") (pintype "unspecified"))
      (node (ref "U30") (pin "8") (pinfunction "VCC_8") (pintype "unspecified"))
      (node (ref "U33") (pin "6") (pinfunction "VDDIO_6") (pintype "unspecified"))
      (node (ref "U33") (pin "8") (pinfunction "VDD_8") (pintype "unspecified"))
      (node (ref "U35") (pin "1") (pinfunction "VCC_1") (pintype "unspecified"))
      (node (ref "U35") (pin "10") (pinfunction "IOVDD_10") (pintype "unspecified"))
      (node (ref "U35") (pin "9") (pinfunction "VREF_9") (pintype "unspecified"))
    )
    (net (code "4") (name "BAT+") (class "Default")
      (node (ref "C113") (pin "2") (pinfunction "2_2") (pintype "unspecified"))
      (node (ref "D21") (pin "2") (pinfunction "A_2") (pintype "unspecified"))
      (node (ref "H1") (pin "2") (pinfunction "2_2") (pintype "unspecified"))
      (node (ref "R125") (pin "1") (pinfunction "1_1") (pintype "unspecified"))
      (node (ref "R93") (pin "1") (pinfunction "1_1") (pintype "input"))
      (node (ref "U21") (pin "2") (pinfunction "S_2") (pintype "unspecified"))
      (node (ref "U9") (pin "5") (pinfunction "BAT_5") (pintype "input"))
    )
    (net (code "5") (name "BAT-") (class "Default")
      (node (ref "C109") (pin "2") (pinfunction "2_2") (pintype "unspecified"))
      (node (ref "H1") (pin "1") (pinfunction "1_1") (pintype "unspecified"))
      (node (ref "U34") (pin "3") (pinfunction "S2_3") (pintype "unspecified"))
      (node (ref "U34") (pin "6") (pinfunction "VSS_6") (pintype "unspecified"))
    )
    (net (code "6") (name "BAT_CHG_DET") (class "Default")
      (node (ref "D20") (pin "2") (pinfunction "A_2") (pintype "unspecified"))
      (node (ref "U28") (pin "47") (pinfunction "PH2_47") (pintype "unspecified"))
    )
    (net (code "7") (name "BAT_DET") (class "Default")
      (node (ref "R95") (pin "2") (pinfunction "2_2") (pintype "input"))
      (node (ref "R96") (pin "1") (pinfunction "1_1") (pintype "input"))
      (node (ref "U28") (pin "14") (pinfunction "PA0_14") (pintype "unspecified"))
    )
    (net (code "8") (name "BOOT0") (class "Default")
      (node (ref "R83") (pin "1") (pinfunction "1_1") (pintype "unspecified"))
      (node (ref "U15") (pin "2") (pinfunction "2_2") (pintype "unspecified"))
      (node (ref "U28") (pin "60") (pinfunction "BOOT0_60") (pintype "unspecified"))
    )
    (net (code "9") (name "BT_RX") (class "Default")
      (node (ref "U13") (pin "7") (pinfunction "TXD_7") (pintype "input"))
      (node (ref "U28") (pin "43") (pinfunction "PA10_43") (pintype "unspecified"))
    )
    (net (code "10") (name "BT_TX") (class "Default")
      (node (ref "U13") (pin "8") (pinfunction "RXD_8") (pintype "input"))
      (node (ref "U28") (pin "42") (pinfunction "PA9_42") (pintype "unspecified"))
    )
    (net (code "11") (name "BUZZ") (class "Default")
      (node (ref "Q10") (pin "1") (pinfunction "G_1") (pintype "unspecified"))
      (node (ref "R104") (pin "1") (pinfunction "1_1") (pintype "unspecified"))
      (node (ref "U28") (pin "38") (pinfunction "PC7_38") (pintype "unspecified"))
    )
    (net (code "12") (name "CC1") (class "Default")
      (node (ref "R91") (pin "1") (pinfunction "1_1") (pintype "input"))
      (node (ref "USB2") (pin "A5") (pinfunction "CC1_A5") (pintype "input"))
    )
    (net (code "13") (name "CC2") (class "Default")
      (node (ref "R92") (pin "1") (pinfunction "1_1") (pintype "input"))
      (node (ref "USB2") (pin "B5") (pinfunction "CC2_B5") (pintype "input"))
    )
    (net (code "14") (name "D+") (class "Default")
      (node (ref "U18") (pin "1") (pinfunction "UD+_1") (pintype "input"))
      (node (ref "USB2") (pin "A6") (pinfunction "DP1_A6") (pintype "input"))
    )
    (net (code "15") (name "D-") (class "Default")
      (node (ref "U18") (pin "2") (pinfunction "UD-_2") (pintype "input"))
      (node (ref "USB2") (pin "A7") (pinfunction "DN1_A7") (pintype "input"))
    )
    (net (code "16") (name "EC_A") (class "Default")
      (node (ref "U28") (pin "56") (pinfunction "PB4_56") (pintype "unspecified"))
      (node (ref "U36") (pin "B") (pinfunction "B_B") (pintype "unspecified"))
    )
    (net (code "17") (name "EC_B") (class "Default")
      (node (ref "U28") (pin "57") (pinfunction "PB5_57") (pintype "unspecified"))
      (node (ref "U36") (pin "D") (pinfunction "D_D") (pintype "unspecified"))
    )
    (net (code "18") (name "EC_KEY") (class "Default")
      (node (ref "D23") (pin "1") (pinfunction "K_1") (pintype "unspecified"))
      (node (ref "D24") (pin "1") (pinfunction "K_1") (pintype "unspecified"))
      (node (ref "U36") (pin "C") (pinfunction "C_C") (pintype "unspecified"))
    )
    (net (code "19") (name "EC_KEY_DET") (class "Default")
      (node (ref "D24") (pin "2") (pinfunction "A_2") (pintype "unspecified"))
      (node (ref "U28") (pin "50") (pinfunction "PA15_50") (pintype "unspecified"))
    )
    (net (code "20") (name "GND") (class "Default")
      (node (ref "10uF1") (pin "2") (pinfunction "2_2") (pintype "input"))
      (node (ref "10uF2") (pin "2") (pinfunction "2_2") (pintype "input"))
      (node (ref "10uF3") (pin "2") (pinfunction "2_2") (pintype "input"))
      (node (ref "10uF4") (pin "2") (pinfunction "2_2") (pintype "input"))
      (node (ref "BUZZER1") (pin "3") (pinfunction "NC_3") (pintype "unspecified"))
      (node (ref "C1") (pin "1") (pinfunction "1_1") (pintype "unspecified"))
      (node (ref "C101") (pin "1") (pinfunction "1_1") (pintype "unspecified"))
      (node (ref "C102") (pin "1") (pinfunction "1_1") (pintype "unspecified"))
      (node (ref "C103") (pin "1") (pinfunction "1_1") (pintype "unspecified"))
      (node (ref "C105") (pin "1") (pinfunction "1_1") (pintype "unspecified"))
      (node (ref "C107") (pin "2") (pinfunction "2_2") (pintype "unspecified"))
      (node (ref "C11") (pin "1") (pinfunction "1_1") (pintype "unspecified"))
      (node (ref "C110") (pin "1") (pinfunction "1_1") (pintype "unspecified"))
      (node (ref "C111") (pin "1") (pinfunction "1_1") (pintype "unspecified"))
      (node (ref "C112") (pin "2") (pinfunction "2_2") (pintype "unspecified"))
      (node (ref "C113") (pin "1") (pinfunction "1_1") (pintype "unspecified"))
      (node (ref "C114") (pin "1") (pinfunction "1_1") (pintype "unspecified"))
      (node (ref "C2") (pin "1") (pinfunction "1_1") (pintype "unspecified"))
      (node (ref "C4") (pin "1") (pinfunction "1_1") (pintype "unspecified"))
      (node (ref "C5") (pin "1") (pinfunction "1_1") (pintype "input"))
      (node (ref "C55") (pin "1") (pinfunction "1_1") (pintype "unspecified"))
      (node (ref "C56") (pin "1") (pinfunction "1_1") (pintype "unspecified"))
      (node (ref "C57") (pin "1") (pinfunction "1_1") (pintype "unspecified"))
      (node (ref "C58") (pin "1") (pinfunction "1_1") (pintype "unspecified"))
      (node (ref "C59") (pin "1") (pinfunction "1_1") (pintype "unspecified"))
      (node (ref "C60") (pin "1") (pinfunction "1_1") (pintype "unspecified"))
      (node (ref "C72") (pin "1") (pinfunction "1_1") (pintype "unspecified"))
      (node (ref "C8") (pin "1") (pinfunction "1_1") (pintype "unspecified"))
      (node (ref "C9") (pin "2") (pinfunction "2_2") (pintype "input"))
      (node (ref "C93") (pin "2") (pinfunction "2_2") (pintype "unspecified"))
      (node (ref "C94") (pin "1") (pinfunction "1_1") (pintype "unspecified"))
      (node (ref "C96") (pin "1") (pinfunction "1_1") (pintype "unspecified"))
      (node (ref "C97") (pin "1") (pinfunction "1_1") (pintype "unspecified"))
      (node (ref "C98") (pin "1") (pinfunction "1_1") (pintype "unspecified"))
      (node (ref "CARD1") (pin "10") (pinfunction "GND_10") (pintype "input"))
      (node (ref "CARD1") (pin "11") (pinfunction "GND_11") (pintype "input"))
      (node (ref "CARD1") (pin "12") (pinfunction "GND_12") (pintype "input"))
      (node (ref "CARD1") (pin "13") (pinfunction "GND_13") (pintype "input"))
      (node (ref "CARD1") (pin "6") (pinfunction "VSS_6") (pintype "input"))
      (node (ref "FPC2") (pin "11") (pinfunction "11_11") (pintype "unspecified"))
      (node (ref "FPC2") (pin "18") (pinfunction "18_18") (pintype "unspecified"))
      (node (ref "H2") (pin "5") (pinfunction "5_5") (pintype "unspecified"))
      (node (ref "Q10") (pin "2") (pinfunction "S_2") (pintype "unspecified"))
      (node (ref "Q11") (pin "2") (pinfunction "S_2") (pintype "unspecified"))
      (node (ref "Q9") (pin "2") (pinfunction "S_2") (pintype "unspecified"))
      (node (ref "R104") (pin "2") (pinfunction "2_2") (pintype "unspecified"))
      (node (ref "R110") (pin "2") (pinfunction "2_2") (pintype "unspecified"))
      (node (ref "R122") (pin "1") (pinfunction "1_1") (pintype "input"))
      (node (ref "R124") (pin "1") (pinfunction "1_1") (pintype "input"))
      (node (ref "R127") (pin "1") (pinfunction "1_1") (pintype "unspecified"))
      (node (ref "R83") (pin "2") (pinfunction "2_2") (pintype "unspecified"))
      (node (ref "R91") (pin "2") (pinfunction "2_2") (pintype "input"))
      (node (ref "R92") (pin "2") (pinfunction "2_2") (pintype "input"))
      (node (ref "R94") (pin "1") (pinfunction "1_1") (pintype "input"))
      (node (ref "R95") (pin "1") (pinfunction "1_1") (pintype "input"))
      (node (ref "RF4") (pin "2") (pinfunction "2_2") (pintype "unspecified"))
      (node (ref "RF4") (pin "3") (pinfunction "3_3") (pintype "unspecified"))
      (node (ref "U13") (pin "3") (pinfunction "GND_3") (pintype "input"))
      (node (ref "U13") (pin "5") (pinfunction "BRTS_5") (pintype "input"))
      (node (ref "U13") (pin "6") (pinfunction "CTS_6") (pintype "input"))
      (node (ref "U17") (pin "1") (pinfunction "GND_1") (pintype "unspecified"))
      (node (ref "U18") (pin "3") (pinfunction "GND_3") (pintype "input"))
      (node (ref "U19") (pin "1") (pinfunction "GND_1") (pintype "unspecified"))
      (node (ref "U27") (pin "2") (pinfunction "GND_2") (pintype "unspecified"))
      (node (ref "U27") (pin "5") (pinfunction "WP_5") (pintype "unspecified"))
      (node (ref "U28") (pin "12") (pinfunction "VSSA/VREF-_12") (pintype "unspecified"))
      (node (ref "U28") (pin "18") (pinfunction "VSS_18") (pintype "unspecified"))
      (node (ref "U28") (pin "28") (pinfunction "PB2_28") (pintype "unspecified"))
      (node (ref "U28") (pin "63") (pinfunction "VSS_63") (pintype "unspecified"))
      (node (ref "U30") (pin "4") (pinfunction "GND_4") (pintype "unspecified"))
      (node (ref "U31") (pin "1") (pinfunction "1_1") (pintype "unspecified"))
      (node (ref "U32") (pin "1") (pinfunction "GND_1") (pintype "unspecified"))
      (node (ref "U32") (pin "10") (pinfunction "GND_10") (pintype "unspecified"))
      (node (ref "U32") (pin "12") (pinfunction "GND_12") (pintype "unspecified"))
      (node (ref "U33") (pin "1") (pinfunction "GND_1") (pintype "unspecified"))
      (node (ref "U33") (pin "5") (pinfunction "SDO_5") (pintype "unspecified"))
      (node (ref "U33") (pin "7") (pinfunction "GND_7") (pintype "unspecified"))
      (node (ref "U34") (pin "2") (pinfunction "S1_2") (pintype "unspecified"))
      (node (ref "U35") (pin "6") (pinfunction "GND_6") (pintype "unspecified"))
      (node (ref "U35") (pin "7") (pinfunction "VBAT_7") (pintype "unspecified"))
      (node (ref "U35") (pin "8") (pinfunction "AUX_8") (pintype "unspecified"))
      (node (ref "U36") (pin "A") (pinfunction "A_A") (pintype "unspecified"))
      (node (ref "U9") (pin "1") (pinfunction "TEMP_1") (pintype "input"))
      (node (ref "U9") (pin "3") (pinfunction "GND_3") (pintype "input"))
      (node (ref "U9") (pin "9") (pinfunction "EP_9") (pintype "input"))
      (node (ref "USB2") (pin "A1B12") (pinfunction "GND_A1B12") (pintype "input"))
      (node (ref "USB2") (pin "B1A12") (pinfunction "GND_B1A12") (pintype "input"))
    )
    (net (code "21") (name "GPS_RX") (class "Default")
      (node (ref "R115") (pin "1") (pinfunction "1_1") (pintype "unspecified"))
      (node (ref "U28") (pin "17") (pinfunction "PA3_17") (pintype "unspecified"))
    )
    (net (code "22") (name "GPS_TX") (class "Default")
      (node (ref "R116") (pin "1") (pinfunction "1_1") (pintype "unspecified"))
      (node (ref "U28") (pin "16") (pinfunction "PA2_16") (pintype "unspecified"))
    )
    (net (code "23") (name "MCU_RX") (class "Default")
      (node (ref "H2") (pin "1") (pinfunction "1_1") (pintype "unspecified"))
      (node (ref "U18") (pin "6") (pinfunction "TXD_6") (pintype "input"))
      (node (ref "U28") (pin "61") (pinfunction "PB8_61") (pintype "unspecified"))
    )
    (net (code "24") (name "MCU_SCL") (class "Default")
      (node (ref "R112") (pin "1") (pinfunction "1_1") (pintype "unspecified"))
      (node (ref "U27") (pin "1") (pinfunction "SCL_1") (pintype "unspecified"))
      (node (ref "U28") (pin "58") (pinfunction "PB6_58") (pintype "unspecified"))
      (node (ref "U33") (pin "4") (pinfunction "SCK_4") (pintype "unspecified"))
    )
    (net (code "25") (name "MCU_SDA") (class "Default")
      (node (ref "R113") (pin "1") (pinfunction "1_1") (pintype "unspecified"))
      (node (ref "U27") (pin "3") (pinfunction "SDA_3") (pintype "unspecified"))
      (node (ref "U28") (pin "59") (pinfunction "PB7_59") (pintype "unspecified"))
      (node (ref "U33") (pin "3") (pinfunction "SDA_3") (pintype "unspecified"))
    )
    (net (code "26") (name "MCU_TX") (class "Default")
      (node (ref "H2") (pin "2") (pinfunction "2_2") (pintype "unspecified"))
      (node (ref "U18") (pin "7") (pinfunction "RXD_7") (pintype "input"))
      (node (ref "U28") (pin "62") (pinfunction "PB9_62") (pintype "unspecified"))
    )
    (net (code "27") (name "Net-(BUZZER1--)") (class "Default")
      (node (ref "BUZZER1") (pin "2") (pinfunction "-_2") (pintype "unspecified"))
      (node (ref "Q10") (pin "3") (pinfunction "D_3") (pintype "unspecified"))
    )
    (net (code "28") (name "Net-(C106-Pad1)") (class "Default")
      (node (ref "C106") (pin "1") (pinfunction "1_1") (pintype "unspecified"))
      (node (ref "L16") (pin "2") (pinfunction "2_2") (pintype "unspecified"))
      (node (ref "RF4") (pin "1") (pinfunction "1_1") (pintype "unspecified"))
    )
    (net (code "29") (name "Net-(CARD1-VDD)") (class "Default")
      (node (ref "C72") (pin "2") (pinfunction "2_2") (pintype "unspecified"))
      (node (ref "CARD1") (pin "4") (pinfunction "VDD_4") (pintype "input"))
      (node (ref "R105") (pin "1") (pinfunction "1_1") (pintype "unspecified"))
    )
    (net (code "30") (name "Net-(D18-A)") (class "Default")
      (node (ref "D18") (pin "2") (pinfunction "A_2") (pintype "unspecified"))
      (node (ref "H3") (pin "2") (pinfunction "2_2") (pintype "unspecified"))
      (node (ref "R120") (pin "1") (pinfunction "1_1") (pintype "input"))
      (node (ref "R122") (pin "2") (pinfunction "2_2") (pintype "input"))
      (node (ref "R123") (pin "1") (pinfunction "1_1") (pintype "input"))
    )
    (net (code "31") (name "Net-(D19-K)") (class "Default")
      (node (ref "D19") (pin "1") (pinfunction "K_1") (pintype "unspecified"))
      (node (ref "Q9") (pin "1") (pinfunction "G_1") (pintype "unspecified"))
      (node (ref "R94") (pin "2") (pinfunction "2_2") (pintype "input"))
    )
    (net (code "32") (name "Net-(D20-K)") (class "Default")
      (node (ref "D20") (pin "1") (pinfunction "K_1") (pintype "unspecified"))
      (node (ref "U7") (pin "1") (pinfunction "K_1") (pintype "unspecified"))
      (node (ref "U9") (pin "7") (pinfunction "CHRG#_7") (pintype "input"))
    )
    (net (code "33") (name "Net-(D21-K)") (class "Default")
      (node (ref "D21") (pin "1") (pinfunction "K_1") (pintype "unspecified"))
      (node (ref "D22") (pin "2") (pinfunction "A_2") (pintype "unspecified"))
    )
    (net (code "34") (name "Net-(D23-A)") (class "Default")
      (node (ref "D23") (pin "2") (pinfunction "A_2") (pintype "unspecified"))
      (node (ref "Q9") (pin "3") (pinfunction "D_3") (pintype "unspecified"))
      (node (ref "R93") (pin "2") (pinfunction "2_2") (pintype "input"))
      (node (ref "U21") (pin "1") (pinfunction "G_1") (pintype "unspecified"))
    )
    (net (code "35") (name "Net-(FPC2-Pad5)") (class "Default")
      (node (ref "FPC2") (pin "5") (pinfunction "5_5") (pintype "unspecified"))
      (node (ref "FPC2") (pin "6") (pinfunction "6_6") (pintype "unspecified"))
      (node (ref "FPC2") (pin "7") (pinfunction "7_7") (pintype "unspecified"))
      (node (ref "FPC2") (pin "8") (pinfunction "8_8") (pintype "unspecified"))
      (node (ref "R111") (pin "2") (pinfunction "2_2") (pintype "input"))
    )
    (net (code "36") (name "Net-(H3-Pad1)") (class "Default")
      (node (ref "H3") (pin "1") (pinfunction "1_1") (pintype "unspecified"))
      (node (ref "R121") (pin "1") (pinfunction "1_1") (pintype "unspecified"))
    )
    (net (code "37") (name "Net-(LED2-A)") (class "Default")
      (node (ref "LED2") (pin "2") (pinfunction "A_2") (pintype "unspecified"))
      (node (ref "R3") (pin "2") (pinfunction "2_2") (pintype "input"))
      (node (ref "U7") (pin "2") (pinfunction "A_2") (pintype "unspecified"))
    )
    (net (code "38") (name "Net-(LED2-K)") (class "Default")
      (node (ref "LED2") (pin "1") (pinfunction "K_1") (pintype "unspecified"))
      (node (ref "U9") (pin "6") (pinfunction "STDBY#_6") (pintype "input"))
    )
    (net (code "39") (name "Net-(LED3-A)") (class "Default")
      (node (ref "LED3") (pin "2") (pinfunction "A_2") (pintype "unspecified"))
      (node (ref "R118") (pin "1") (pinfunction "1_1") (pintype "input"))
    )
    (net (code "40") (name "Net-(LED3-K)") (class "Default")
      (node (ref "LED3") (pin "1") (pinfunction "K_1") (pintype "unspecified"))
      (node (ref "U32") (pin "4") (pinfunction "PPS_4") (pintype "unspecified"))
    )
    (net (code "41") (name "Net-(Q11-D)") (class "Default")
      (node (ref "Q11") (pin "3") (pinfunction "D_3") (pintype "unspecified"))
      (node (ref "R111") (pin "1") (pinfunction "1_1") (pintype "input"))
    )
    (net (code "42") (name "Net-(U9-CE)") (class "Default")
      (node (ref "C1") (pin "2") (pinfunction "2_2") (pintype "unspecified"))
      (node (ref "C2") (pin "2") (pinfunction "2_2") (pintype "unspecified"))
      (node (ref "C8") (pin "2") (pinfunction "2_2") (pintype "unspecified"))
      (node (ref "R22") (pin "2") (pinfunction "2_2") (pintype "unspecified"))
      (node (ref "R3") (pin "1") (pinfunction "1_1") (pintype "input"))
      (node (ref "U9") (pin "4") (pinfunction "VCC_4") (pintype "input"))
      (node (ref "U9") (pin "8") (pinfunction "CE_8") (pintype "input"))
    )
    (net (code "43") (name "Net-(U9-PROG)") (class "Default")
      (node (ref "R127") (pin "2") (pinfunction "2_2") (pintype "unspecified"))
      (node (ref "U9") (pin "2") (pinfunction "PROG_2") (pintype "input"))
    )
    (net (code "44") (name "Net-(U13-LINK)") (class "Default")
      (node (ref "U13") (pin "1") (pinfunction "LINK_1") (pintype "input"))
      (node (ref "U14") (pin "1") (pinfunction "K_1") (pintype "unspecified"))
    )
    (net (code "45") (name "Net-(U14-A)") (class "Default")
      (node (ref "R81") (pin "2") (pinfunction "2_2") (pintype "unspecified"))
      (node (ref "U14") (pin "2") (pinfunction "A_2") (pintype "unspecified"))
    )
    (net (code "46") (name "Net-(U18-V3)") (class "Default")
      (node (ref "C9") (pin "1") (pinfunction "1_1") (pintype "input"))
      (node (ref "U18") (pin "8") (pinfunction "V3_8") (pintype "input"))
    )
    (net (code "47") (name "Net-(U19-VIN)") (class "Default")
      (node (ref "10uF3") (pin "1") (pinfunction "1_1") (pintype "input"))
      (node (ref "C59") (pin "2") (pinfunction "2_2") (pintype "unspecified"))
      (node (ref "L11") (pin "2") (pinfunction "2_2") (pintype "unspecified"))
      (node (ref "U19") (pin "3") (pinfunction "VIN_3") (pintype "unspecified"))
    )
    (net (code "48") (name "Net-(U32-GNSS_ANT)") (class "Default")
      (node (ref "C106") (pin "2") (pinfunction "2_2") (pintype "unspecified"))
      (node (ref "U32") (pin "11") (pinfunction "GNSS_ANT_11") (pintype "unspecified"))
    )
    (net (code "49") (name "Net-(U32-RXD)") (class "Default")
      (node (ref "R116") (pin "2") (pinfunction "2_2") (pintype "unspecified"))
      (node (ref "U32") (pin "3") (pinfunction "RXD_3") (pintype "unspecified"))
    )
    (net (code "50") (name "Net-(U32-TXD)") (class "Default")
      (node (ref "R115") (pin "2") (pinfunction "2_2") (pintype "unspecified"))
      (node (ref "U32") (pin "2") (pinfunction "TXD_2") (pintype "unspecified"))
    )
    (net (code "51") (name "Net-(U32-VCC_RF)") (class "Default")
      (node (ref "C107") (pin "1") (pinfunction "1_1") (pintype "unspecified"))
      (node (ref "L16") (pin "1") (pinfunction "1_1") (pintype "unspecified"))
      (node (ref "U32") (pin "14") (pinfunction "VCC_RF_14") (pintype "unspecified"))
    )
    (net (code "52") (name "Net-(U34-V-)") (class "Default")
      (node (ref "R124") (pin "2") (pinfunction "2_2") (pintype "input"))
      (node (ref "U34") (pin "1") (pinfunction "V-_1") (pintype "unspecified"))
    )
    (net (code "53") (name "Net-(U34-VDD)") (class "Default")
      (node (ref "C109") (pin "1") (pinfunction "1_1") (pintype "unspecified"))
      (node (ref "R125") (pin "2") (pinfunction "2_2") (pintype "unspecified"))
      (node (ref "U34") (pin "5") (pinfunction "VDD_5") (pintype "unspecified"))
    )
    (net (code "54") (name "OTG_D+") (class "Default")
      (node (ref "U28") (pin "45") (pinfunction "PA12_45") (pintype "unspecified"))
      (node (ref "USB2") (pin "B6") (pinfunction "DP2_B6") (pintype "input"))
    )
    (net (code "55") (name "OTG_D-") (class "Default")
      (node (ref "U28") (pin "44") (pinfunction "PA11_44") (pintype "unspecified"))
      (node (ref "USB2") (pin "B7") (pinfunction "DN2_B7") (pintype "input"))
    )
    (net (code "56") (name "PWR_EN") (class "Default")
      (node (ref "D19") (pin "2") (pinfunction "A_2") (pintype "unspecified"))
      (node (ref "U28") (pin "54") (pinfunction "PD2_54") (pintype "unspecified"))
    )
    (net (code "57") (name "QSPI_CS") (class "Default")
      (node (ref "U28") (pin "52") (pinfunction "PC11_52") (pintype "unspecified"))
      (node (ref "U30") (pin "1") (pinfunction "CS#_1") (pintype "unspecified"))
    )
    (net (code "58") (name "QSPI_IO0") (class "Default")
      (node (ref "U28") (pin "40") (pinfunction "PC9_40") (pintype "unspecified"))
      (node (ref "U30") (pin "5") (pinfunction "DI(IO0)_5") (pintype "unspecified"))
    )
    (net (code "59") (name "QSPI_IO1") (class "Default")
      (node (ref "U28") (pin "51") (pinfunction "PC10_51") (pintype "unspecified"))
      (node (ref "U30") (pin "2") (pinfunction "DO(IO1)_2") (pintype "unspecified"))
    )
    (net (code "60") (name "QSPI_IO2") (class "Default")
      (node (ref "U28") (pin "39") (pinfunction "PC8_39") (pintype "unspecified"))
      (node (ref "U30") (pin "3") (pinfunction "WP#(IO2)_3") (pintype "unspecified"))
    )
    (net (code "61") (name "QSPI_IO3") (class "Default")
      (node (ref "U28") (pin "55") (pinfunction "PB3_55") (pintype "unspecified"))
      (node (ref "U30") (pin "7") (pinfunction "HOLD#orRESET#(IO3)_7") (pintype "unspecified"))
    )
    (net (code "62") (name "QSPI_SCK") (class "Default")
      (node (ref "U28") (pin "27") (pinfunction "PB1_27") (pintype "unspecified"))
      (node (ref "U30") (pin "6") (pinfunction "CLK_6") (pintype "unspecified"))
    )
    (net (code "63") (name "RST") (class "Default")
      (node (ref "C98") (pin "2") (pinfunction "2_2") (pintype "unspecified"))
      (node (ref "R114") (pin "2") (pinfunction "2_2") (pintype "unspecified"))
      (node (ref "U28") (pin "7") (pinfunction "NRST_7") (pintype "unspecified"))
      (node (ref "U31") (pin "2") (pinfunction "2_2") (pintype "unspecified"))
    )
    (net (code "64") (name "SCR_BLK") (class "Default")
      (node (ref "Q11") (pin "1") (pinfunction "G_1") (pintype "unspecified"))
      (node (ref "R110") (pin "1") (pinfunction "1_1") (pintype "unspecified"))
      (node (ref "U28") (pin "29") (pinfunction "PB10_29") (pintype "unspecified"))
    )
    (net (code "65") (name "SCR_CS") (class "Default")
      (node (ref "FPC2") (pin "14") (pinfunction "14_14") (pintype "unspecified"))
      (node (ref "U28") (pin "26") (pinfunction "PB0_26") (pintype "unspecified"))
    )
    (net (code "66") (name "SCR_DC") (class "Default")
      (node (ref "FPC2") (pin "15") (pinfunction "15_15") (pintype "unspecified"))
      (node (ref "U28") (pin "20") (pinfunction "PA4_20") (pintype "unspecified"))
    )
    (net (code "67") (name "SCR_RES") (class "Default")
      (node (ref "FPC2") (pin "17") (pinfunction "17_17") (pintype "unspecified"))
      (node (ref "U28") (pin "30") (pinfunction "PB11_30") (pintype "unspecified"))
    )
    (net (code "68") (name "SCR_SCL") (class "Default")
      (node (ref "FPC2") (pin "16") (pinfunction "16_16") (pintype "unspecified"))
      (node (ref "U28") (pin "21") (pinfunction "PA5_21") (pintype "unspecified"))
    )
    (net (code "69") (name "SCR_SDA") (class "Default")
      (node (ref "FPC2") (pin "13") (pinfunction "13_13") (pintype "unspecified"))
      (node (ref "U28") (pin "23") (pinfunction "PA7_23") (pintype "unspecified"))
    )
    (net (code "70") (name "SD_CD") (class "Default")
      (node (ref "CARD1") (pin "9") (pinfunction "CD_9") (pintype "input"))
      (node (ref "U28") (pin "41") (pinfunction "PA8_41") (pintype "unspecified"))
    )
    (net (code "71") (name "SD_CK") (class "Default")
      (node (ref "CARD1") (pin "5") (pinfunction "CLK(SCLK)_5") (pintype "input"))
      (node (ref "U28") (pin "24") (pinfunction "PC4_24") (pintype "unspecified"))
    )
    (net (code "72") (name "SD_CMD") (class "Default")
      (node (ref "CARD1") (pin "3") (pinfunction "CMD(DI)_3") (pintype "input"))
      (node (ref "U28") (pin "25") (pinfunction "PC5_25") (pintype "unspecified"))
    )
    (net (code "73") (name "SD_D0") (class "Default")
      (node (ref "CARD1") (pin "7") (pinfunction "DAT0(D0)_7") (pintype "bidirectional"))
      (node (ref "U28") (pin "8") (pinfunction "PC0_8") (pintype "unspecified"))
    )
    (net (code "74") (name "SD_D1") (class "Default")
      (node (ref "CARD1") (pin "8") (pinfunction "DAT1(RSV)_8") (pintype "bidirectional"))
      (node (ref "U28") (pin "9") (pinfunction "PC1_9") (pintype "unspecified"))
    )
    (net (code "75") (name "SD_D2") (class "Default")
      (node (ref "CARD1") (pin "1") (pinfunction "DAT2(RSV)_1") (pintype "bidirectional"))
      (node (ref "U28") (pin "10") (pinfunction "PC2_10") (pintype "unspecified"))
    )
    (net (code "76") (name "SD_D3") (class "Default")
      (node (ref "CARD1") (pin "2") (pinfunction "CDDAT3(CS)_2") (pintype "bidirectional"))
      (node (ref "U28") (pin "11") (pinfunction "PC3_11") (pintype "unspecified"))
    )
    (net (code "77") (name "SWCLK") (class "Default")
      (node (ref "H2") (pin "3") (pinfunction "3_3") (pintype "unspecified"))
      (node (ref "U28") (pin "49") (pinfunction "PA14_49") (pintype "unspecified"))
    )
    (net (code "78") (name "SWDIO") (class "Default")
      (node (ref "H2") (pin "4") (pinfunction "4_4") (pintype "unspecified"))
      (node (ref "U28") (pin "46") (pinfunction "PA13_46") (pintype "unspecified"))
    )
    (net (code "79") (name "TP_CS") (class "Default")
      (node (ref "U28") (pin "33") (pinfunction "PB12_33") (pintype "unspecified"))
      (node (ref "U35") (pin "15") (pinfunction "CS#_15") (pintype "unspecified"))
    )
    (net (code "80") (name "TP_IRQ") (class "Default")
      (node (ref "R126") (pin "2") (pinfunction "2_2") (pintype "unspecified"))
      (node (ref "U28") (pin "37") (pinfunction "PC6_37") (pintype "unspecified"))
      (node (ref "U35") (pin "11") (pinfunction "PENIRQ#_11") (pintype "unspecified"))
    )
    (net (code "81") (name "TP_SCL") (class "Default")
      (node (ref "U28") (pin "34") (pinfunction "PB13_34") (pintype "unspecified"))
      (node (ref "U35") (pin "16") (pinfunction "DCLK_16") (pintype "unspecified"))
    )
    (net (code "82") (name "TP_SDA") (class "Default")
      (node (ref "U28") (pin "36") (pinfunction "PB15_36") (pintype "unspecified"))
      (node (ref "U35") (pin "14") (pinfunction "DIN_14") (pintype "unspecified"))
    )
    (net (code "83") (name "TP_SDO") (class "Default")
      (node (ref "U28") (pin "35") (pinfunction "PB14_35") (pintype "unspecified"))
      (node (ref "U35") (pin "12") (pinfunction "DOUT_12") (pintype "unspecified"))
    )
    (net (code "84") (name "VBAT_OUT") (class "Default")
      (node (ref "L10") (pin "1") (pinfunction "1_1") (pintype "unspecified"))
      (node (ref "L11") (pin "1") (pinfunction "1_1") (pintype "unspecified"))
      (node (ref "U21") (pin "3") (pinfunction "D_3") (pintype "unspecified"))
    )
    (net (code "85") (name "VCC_RTC") (class "Default")
      (node (ref "C105") (pin "2") (pinfunction "2_2") (pintype "unspecified"))
      (node (ref "C114") (pin "2") (pinfunction "2_2") (pintype "unspecified"))
      (node (ref "C96") (pin "2") (pinfunction "2_2") (pintype "unspecified"))
      (node (ref "D22") (pin "1") (pinfunction "K_1") (pintype "unspecified"))
      (node (ref "U28") (pin "1") (pinfunction "VBAT_1") (pintype "unspecified"))
      (node (ref "U32") (pin "6") (pinfunction "VCC_BACKUP_6") (pintype "unspecified"))
    )
    (net (code "86") (name "VIBRATOR") (class "Default")
      (node (ref "D18") (pin "1") (pinfunction "K_1") (pintype "unspecified"))
      (node (ref "R120") (pin "2") (pinfunction "2_2") (pintype "input"))
      (node (ref "R121") (pin "2") (pinfunction "2_2") (pintype "unspecified"))
      (node (ref "U28") (pin "15") (pinfunction "PA1_15") (pintype "unspecified"))
    )
    (net (code "87") (name "VIN") (class "Default")
      (node (ref "10uF1") (pin "1") (pinfunction "1_1") (pintype "input"))
      (node (ref "C11") (pin "2") (pinfunction "2_2") (pintype "unspecified"))
      (node (ref "L10") (pin "2") (pinfunction "2_2") (pintype "unspecified"))
      (node (ref "R96") (pin "2") (pinfunction "2_2") (pintype "input"))
      (node (ref "U17") (pin "3") (pinfunction "VIN_3") (pintype "unspecified"))
    )
    (net (code "88") (name "X+") (class "Default")
      (node (ref "FPC2") (pin "2") (pinfunction "2_2") (pintype "unspecified"))
      (node (ref "U35") (pin "2") (pinfunction "XP_2") (pintype "unspecified"))
    )
    (net (code "89") (name "X-") (class "Default")
      (node (ref "FPC2") (pin "4") (pinfunction "4_4") (pintype "unspecified"))
      (node (ref "U35") (pin "4") (pinfunction "XN_4") (pintype "unspecified"))
    )
    (net (code "90") (name "Y+") (class "Default")
      (node (ref "FPC2") (pin "1") (pinfunction "1_1") (pintype "unspecified"))
      (node (ref "U35") (pin "3") (pinfunction "YP_3") (pintype "unspecified"))
    )
    (net (code "91") (name "Y-") (class "Default")
      (node (ref "FPC2") (pin "3") (pinfunction "3_3") (pintype "unspecified"))
      (node (ref "U35") (pin "5") (pinfunction "YN_5") (pintype "unspecified"))
    )
    (net (code "92") (name "unconnected-(FPC2-Pad12)") (class "Default")
      (node (ref "FPC2") (pin "12") (pinfunction "12_12") (pintype "unspecified+no_connect"))
    )
    (net (code "93") (name "unconnected-(FPC2-Pad19)") (class "Default")
      (node (ref "FPC2") (pin "19") (pinfunction "19_19") (pintype "unspecified+no_connect"))
    )
    (net (code "94") (name "unconnected-(FPC2-Pad20)") (class "Default")
      (node (ref "FPC2") (pin "20") (pinfunction "20_20") (pintype "unspecified+no_connect"))
    )
    (net (code "95") (name "unconnected-(U18-RTS#-Pad4)") (class "Default")
      (node (ref "U18") (pin "4") (pinfunction "RTS#_4") (pintype "input+no_connect"))
    )
    (net (code "96") (name "unconnected-(U28-PA6-Pad22)") (class "Default")
      (node (ref "U28") (pin "22") (pinfunction "PA6_22") (pintype "unspecified+no_connect"))
    )
    (net (code "97") (name "unconnected-(U28-PC12-Pad53)") (class "Default")
      (node (ref "U28") (pin "53") (pinfunction "PC12_53") (pintype "unspecified+no_connect"))
    )
    (net (code "98") (name "unconnected-(U28-PC13-Pad2)") (class "Default")
      (node (ref "U28") (pin "2") (pinfunction "PC13_2") (pintype "unspecified+no_connect"))
    )
    (net (code "99") (name "unconnected-(U28-PC14-Pad3)") (class "Default")
      (node (ref "U28") (pin "3") (pinfunction "PC14_3") (pintype "unspecified+no_connect"))
    )
    (net (code "100") (name "unconnected-(U28-PC15-Pad4)") (class "Default")
      (node (ref "U28") (pin "4") (pinfunction "PC15_4") (pintype "unspecified+no_connect"))
    )
    (net (code "101") (name "unconnected-(U28-PH0-Pad5)") (class "Default")
      (node (ref "U28") (pin "5") (pinfunction "PH0_5") (pintype "unspecified+no_connect"))
    )
    (net (code "102") (name "unconnected-(U28-PH1-Pad6)") (class "Default")
      (node (ref "U28") (pin "6") (pinfunction "PH1_6") (pintype "unspecified+no_connect"))
    )
    (net (code "103") (name "unconnected-(U28-PH3-Pad31)") (class "Default")
      (node (ref "U28") (pin "31") (pinfunction "PH3_31") (pintype "unspecified+no_connect"))
    )
    (net (code "104") (name "unconnected-(U32-ANT_ON-Pad13)") (class "Default")
      (node (ref "U32") (pin "13") (pinfunction "ANT_ON_13") (pintype "unspecified+no_connect"))
    )
    (net (code "105") (name "unconnected-(U32-RESERVED-Pad7)") (class "Default")
      (node (ref "U32") (pin "7") (pinfunction "RESERVED_7") (pintype "unspecified+no_connect"))
    )
    (net (code "106") (name "unconnected-(U32-RESERVED-Pad15)") (class "Default")
      (node (ref "U32") (pin "15") (pinfunction "RESERVED_15") (pintype "unspecified+no_connect"))
    )
    (net (code "107") (name "unconnected-(U32-RESERVED-Pad16)") (class "Default")
      (node (ref "U32") (pin "16") (pinfunction "RESERVED_16") (pintype "unspecified+no_connect"))
    )
    (net (code "108") (name "unconnected-(U32-RESERVED-Pad17)") (class "Default")
      (node (ref "U32") (pin "17") (pinfunction "RESERVED_17") (pintype "unspecified+no_connect"))
    )
    (net (code "109") (name "unconnected-(U32-RESET-Pad9)") (class "Default")
      (node (ref "U32") (pin "9") (pinfunction "RESET_9") (pintype "unspecified+no_connect"))
    )
    (net (code "110") (name "unconnected-(U32-SET-Pad18)") (class "Default")
      (node (ref "U32") (pin "18") (pinfunction "SET_18") (pintype "unspecified+no_connect"))
    )
    (net (code "111") (name "unconnected-(U32-WAKE_UP-Pad5)") (class "Default")
      (node (ref "U32") (pin "5") (pinfunction "WAKE_UP_5") (pintype "unspecified+no_connect"))
    )
    (net (code "112") (name "unconnected-(U33-CSB-Pad2)") (class "Default")
      (node (ref "U33") (pin "2") (pinfunction "CSB_2") (pintype "unspecified+no_connect"))
    )
    (net (code "113") (name "unconnected-(U34-D-Pad4)") (class "Default")
      (node (ref "U34") (pin "4") (pinfunction "D_4") (pintype "unspecified+no_connect"))
    )
    (net (code "114") (name "unconnected-(U35-BUSY-Pad13)") (class "Default")
      (node (ref "U35") (pin "13") (pinfunction "BUSY_13") (pintype "unspecified+no_connect"))
    )
    (net (code "115") (name "unconnected-(U36-Pad0)") (class "Default")
      (node (ref "U36") (pin "0") (pinfunction "0_0") (pintype "unspecified+no_connect"))
    )
    (net (code "116") (name "unconnected-(USB2-PadEP)") (class "Default")
      (node (ref "USB2") (pin "EP") (pinfunction "EP_EP") (pintype "input+no_connect"))
    )
    (net (code "117") (name "unconnected-(USB2-SBU1-PadA8)") (class "Default")
      (node (ref "USB2") (pin "A8") (pinfunction "SBU1_A8") (pintype "input+no_connect"))
    )
    (net (code "118") (name "unconnected-(USB2-SBU2-PadB8)") (class "Default")
      (node (ref "USB2") (pin "B8") (pinfunction "SBU2_B8") (pintype "input+no_connect"))
    )
    (net (code "119") (name "unconnected-(X1-Pad1)") (class "Default")
      (node (ref "X1") (pin "1") (pinfunction "1_1") (pintype "unspecified"))
    )
    (net (code "120") (name "unconnected-(X1-Pad2)") (class "Default")
      (node (ref "X1") (pin "2") (pinfunction "2_2") (pintype "unspecified"))
    )
    (net (code "121") (name "unconnected-(X1-Pad3)") (class "Default")
      (node (ref "X1") (pin "3") (pinfunction "3_3") (pintype "unspecified"))
    )
    (net (code "122") (name "unconnected-(X1-Pad4)") (class "Default")
      (node (ref "X1") (pin "4") (pinfunction "4_4") (pintype "unspecified"))
    )
    (net (code "123") (name "unconnected-(X1-Pad5)") (class "Default")
      (node (ref "X1") (pin "5") (pinfunction "5_5") (pintype "unspecified"))
    )
    (net (code "124") (name "unconnected-(X1-Pad6)") (class "Default")
      (node (ref "X1") (pin "6") (pinfunction "6_6") (pintype "unspecified"))
    )
    (net (code "125") (name "unconnected-(X1-Pad7)") (class "Default")
      (node (ref "X1") (pin "7") (pinfunction "7_7") (pintype "unspecified"))
    )
    (net (code "126") (name "unconnected-(X1-Pad8)") (class "Default")
      (node (ref "X1") (pin "8") (pinfunction "8_8") (pintype "unspecified"))
    )
    (net (code "127") (name "unconnected-(X1-Pad9)") (class "Default")
      (node (ref "X1") (pin "9") (pinfunction "9_9") (pintype "unspecified"))
    )
    (net (code "128") (name "unconnected-(X1-Pad10)") (class "Default")
      (node (ref "X1") (pin "10") (pinfunction "10_10") (pintype "unspecified"))
    )
    (net (code "129") (name "unconnected-(X1-Pad11)") (class "Default")
      (node (ref "X1") (pin "11") (pinfunction "11_11") (pintype "unspecified"))
    )
    (net (code "130") (name "unconnected-(X1-Pad12)") (class "Default")
      (node (ref "X1") (pin "12") (pinfunction "12_12") (pintype "unspecified"))
    )
    (net (code "131") (name "unconnected-(X1-Pad13)") (class "Default")
      (node (ref "X1") (pin "13") (pinfunction "13_13") (pintype "unspecified"))
    )
    (net (code "132") (name "unconnected-(X1-Pad14)") (class "Default")
      (node (ref "X1") (pin "14") (pinfunction "14_14") (pintype "unspecified"))
    )
    (net (code "133") (name "unconnected-(X1-Pad15)") (class "Default")
      (node (ref "X1") (pin "15") (pinfunction "15_15") (pintype "unspecified"))
    )
    (net (code "134") (name "unconnected-(X1-Pad16)") (class "Default")
      (node (ref "X1") (pin "16") (pinfunction "16_16") (pintype "unspecified"))
    )
    (net (code "135") (name "unconnected-(X1-Pad17)") (class "Default")
      (node (ref "X1") (pin "17") (pinfunction "17_17") (pintype "unspecified"))
    )
    (net (code "136") (name "unconnected-(X1-Pad18)") (class "Default")
      (node (ref "X1") (pin "18") (pinfunction "18_18") (pintype "unspecified"))
    )
    (net (code "137") (name "unconnected-(X1-Pad19)") (class "Default")
      (node (ref "X1") (pin "19") (pinfunction "19_19") (pintype "unspecified"))
    )
    (net (code "138") (name "unconnected-(X1-Pad20)") (class "Default")
      (node (ref "X1") (pin "20") (pinfunction "20_20") (pintype "unspecified"))
    )
  )
)
